# SolarPanel.net
KiCad netlist of a schematic drawn in EAGLE
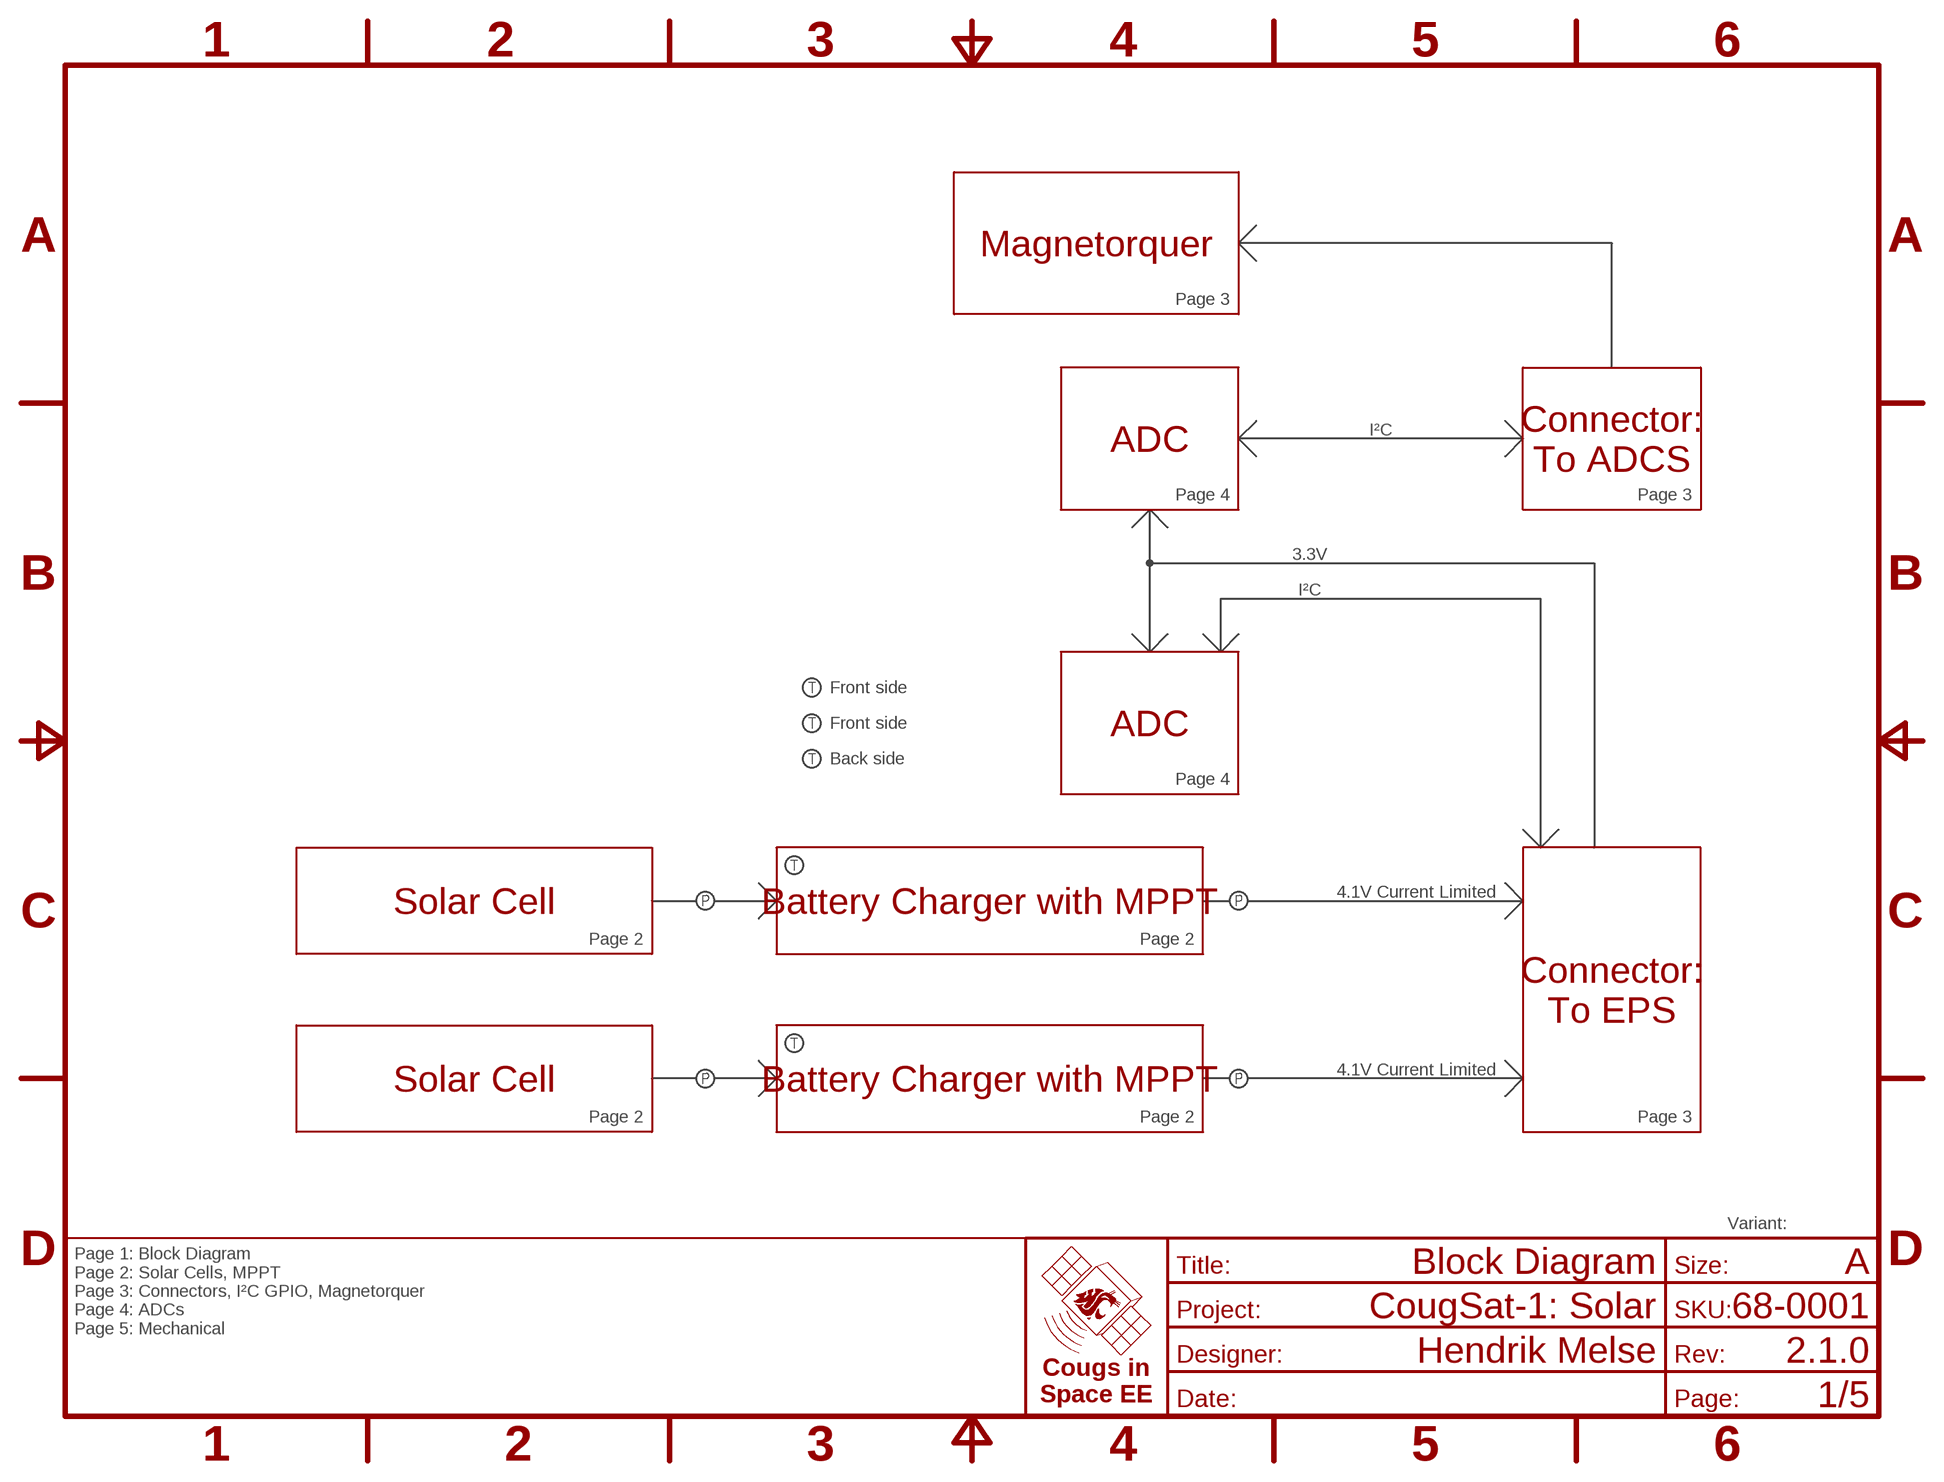
[diagram p0: schematic, sheet 1]
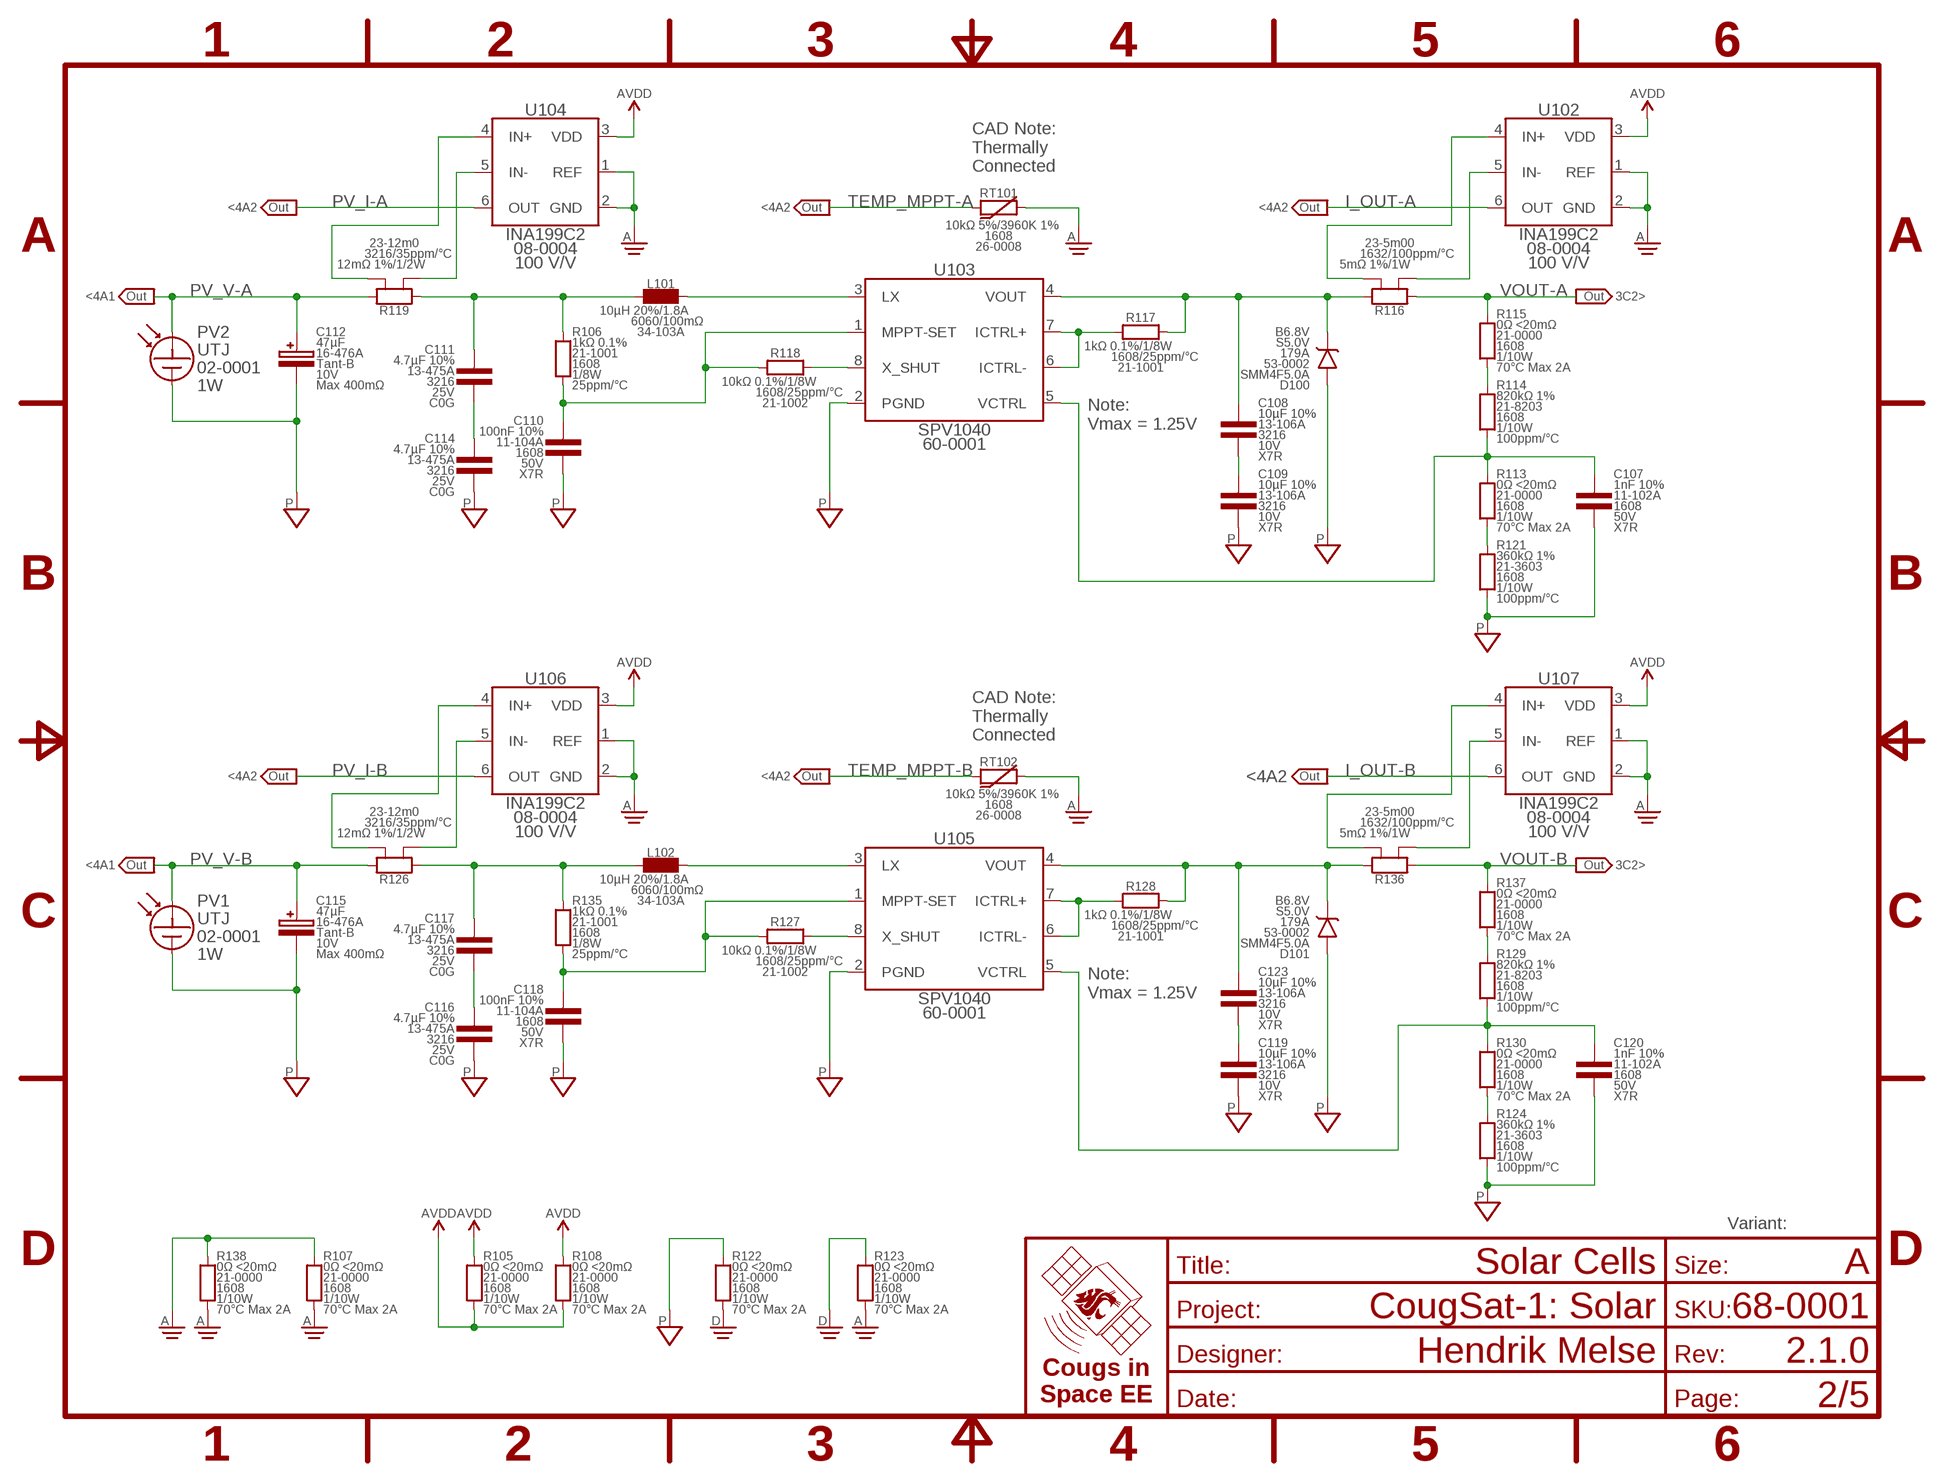
[diagram p1: schematic, sheet 2]
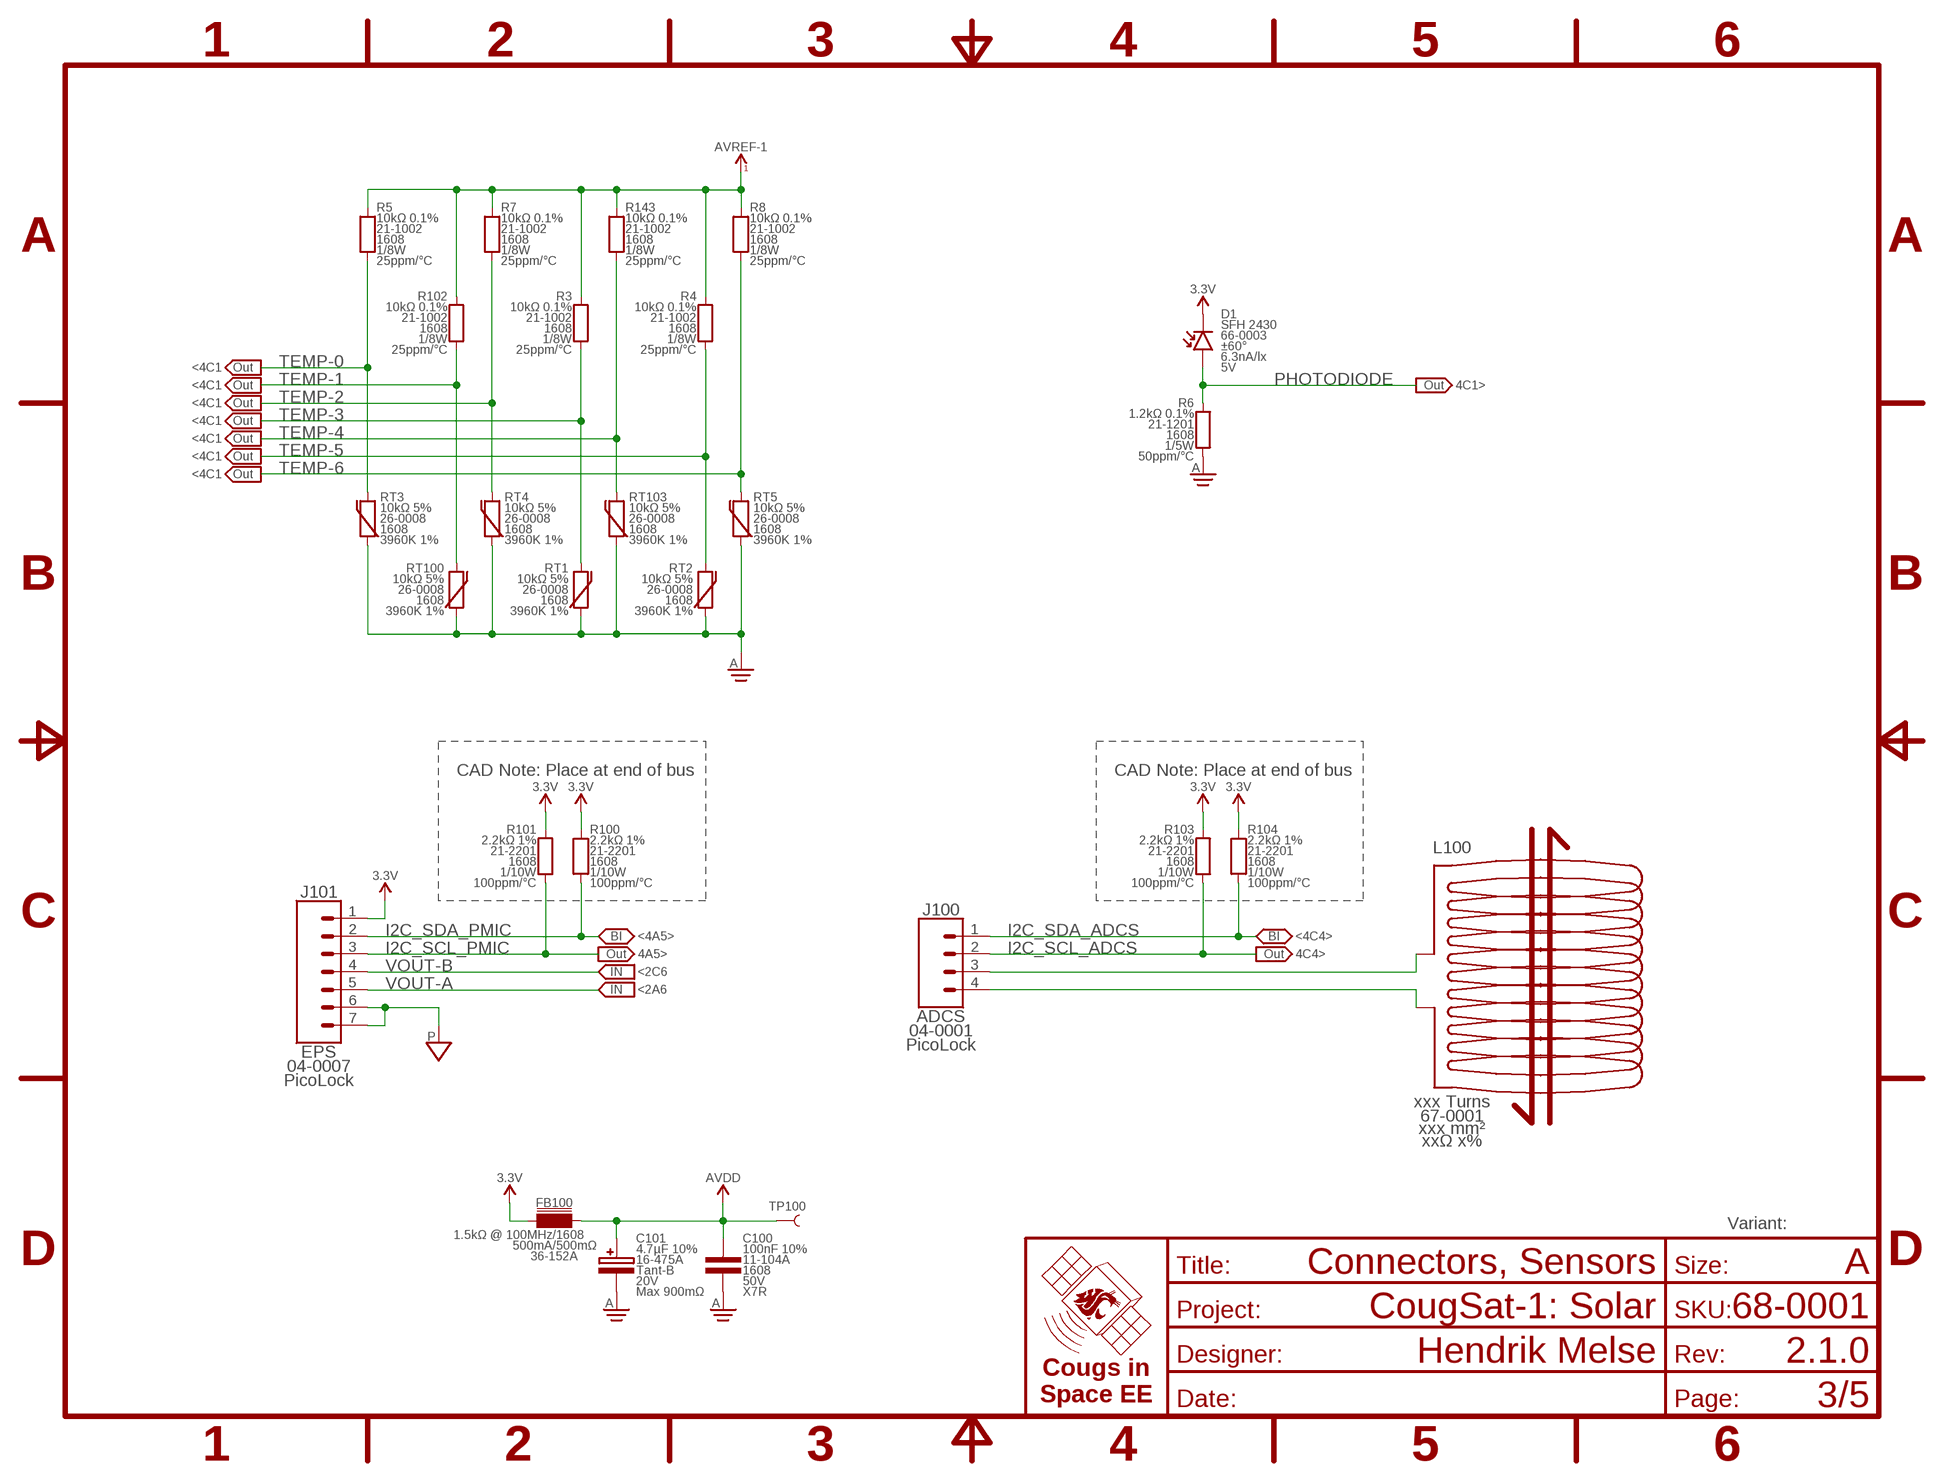
[diagram p2: schematic, sheet 3]
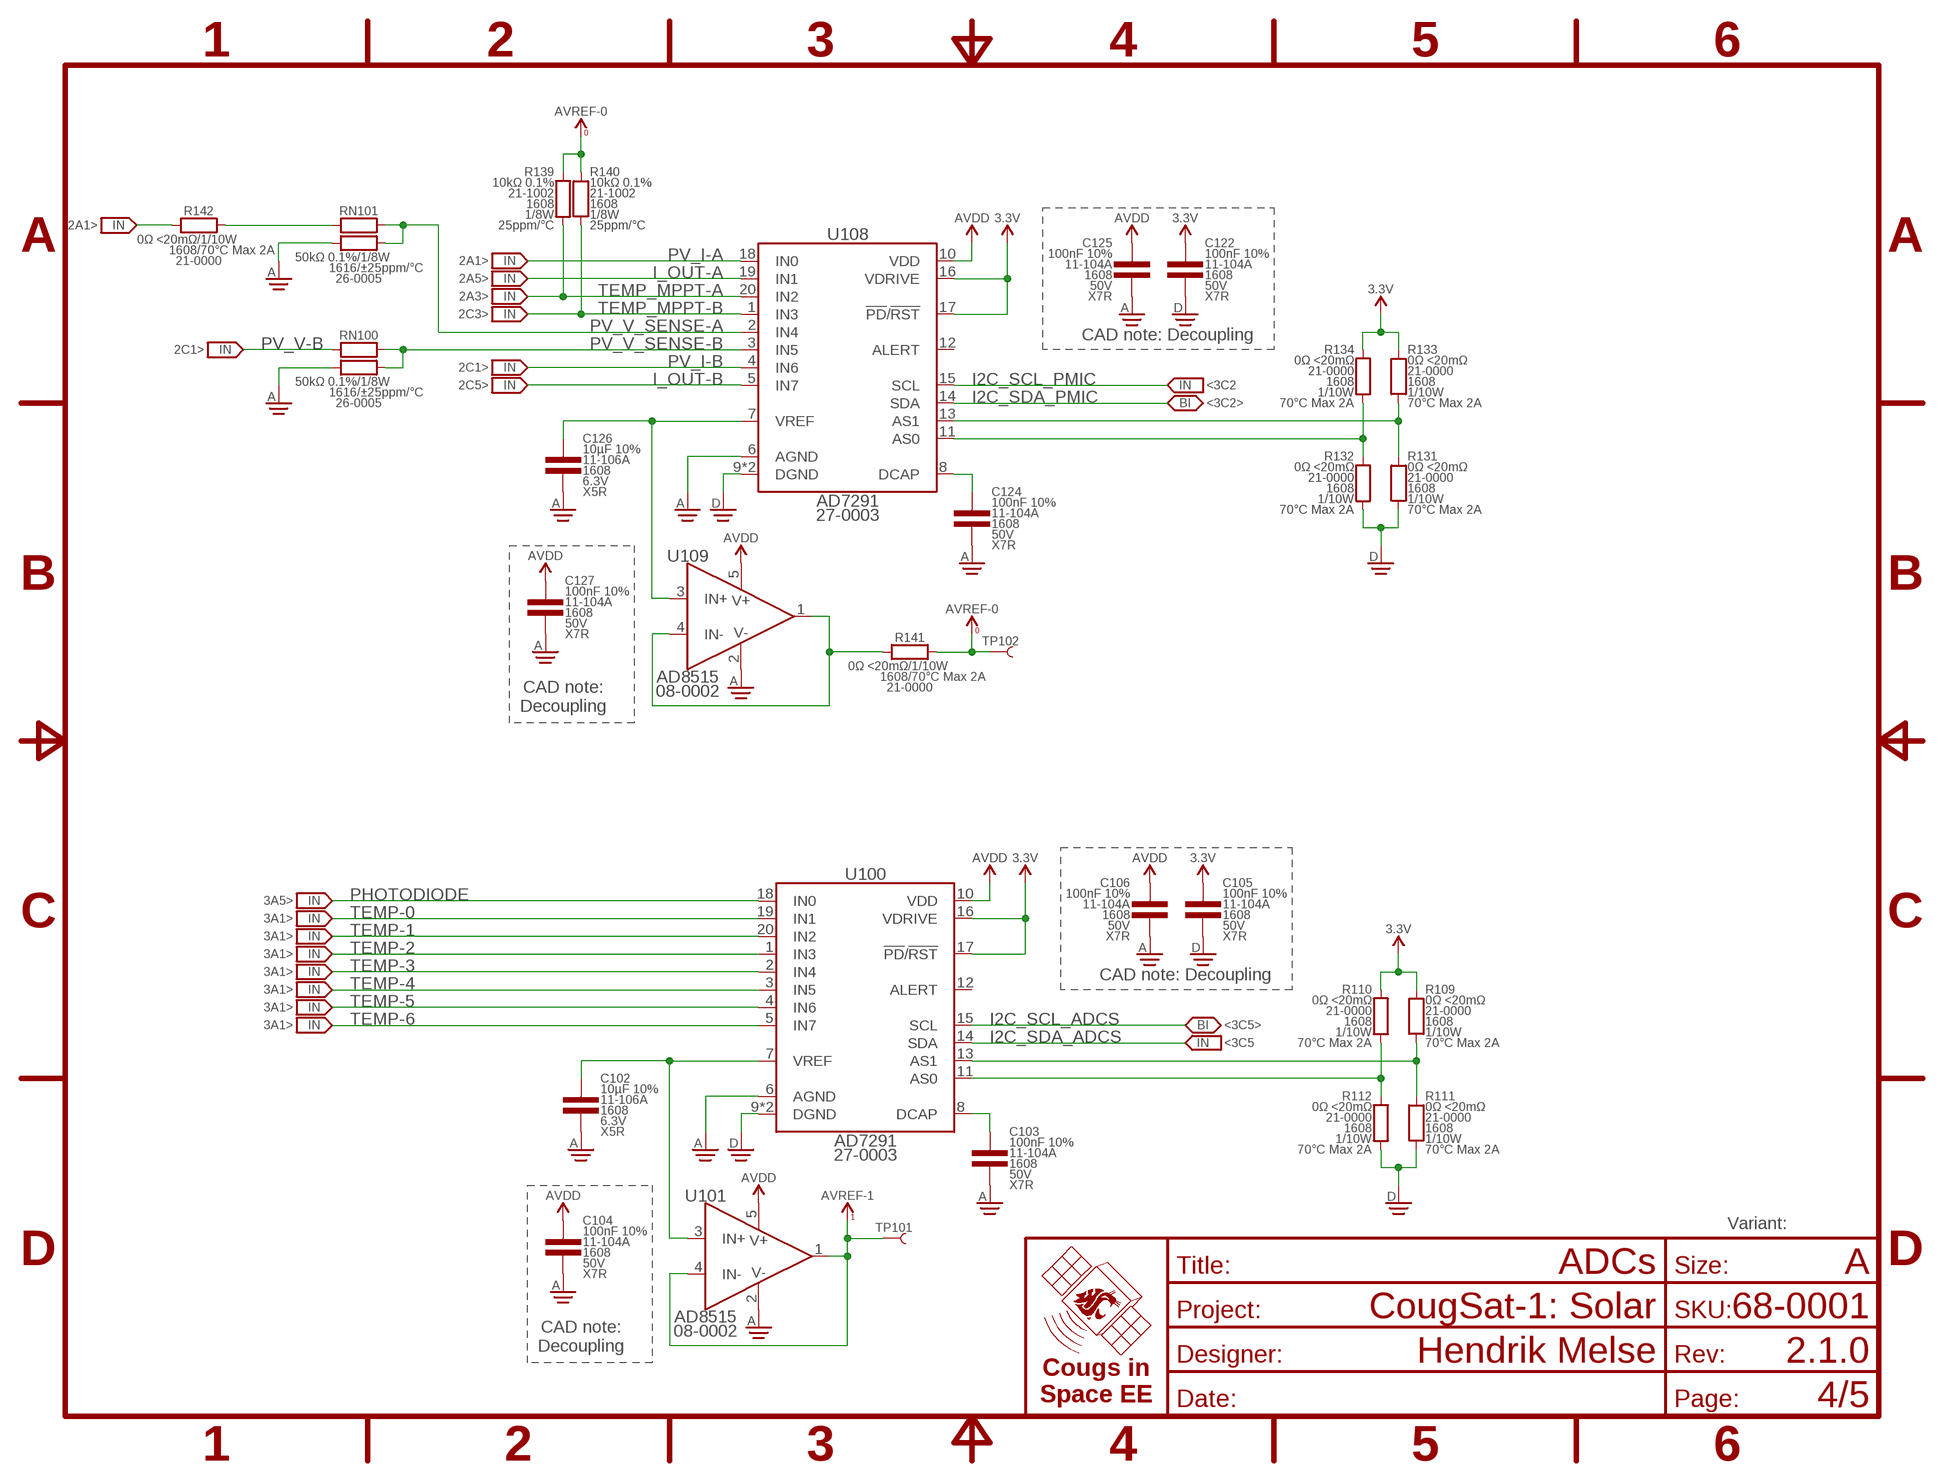
[diagram p3: schematic, sheet 4]
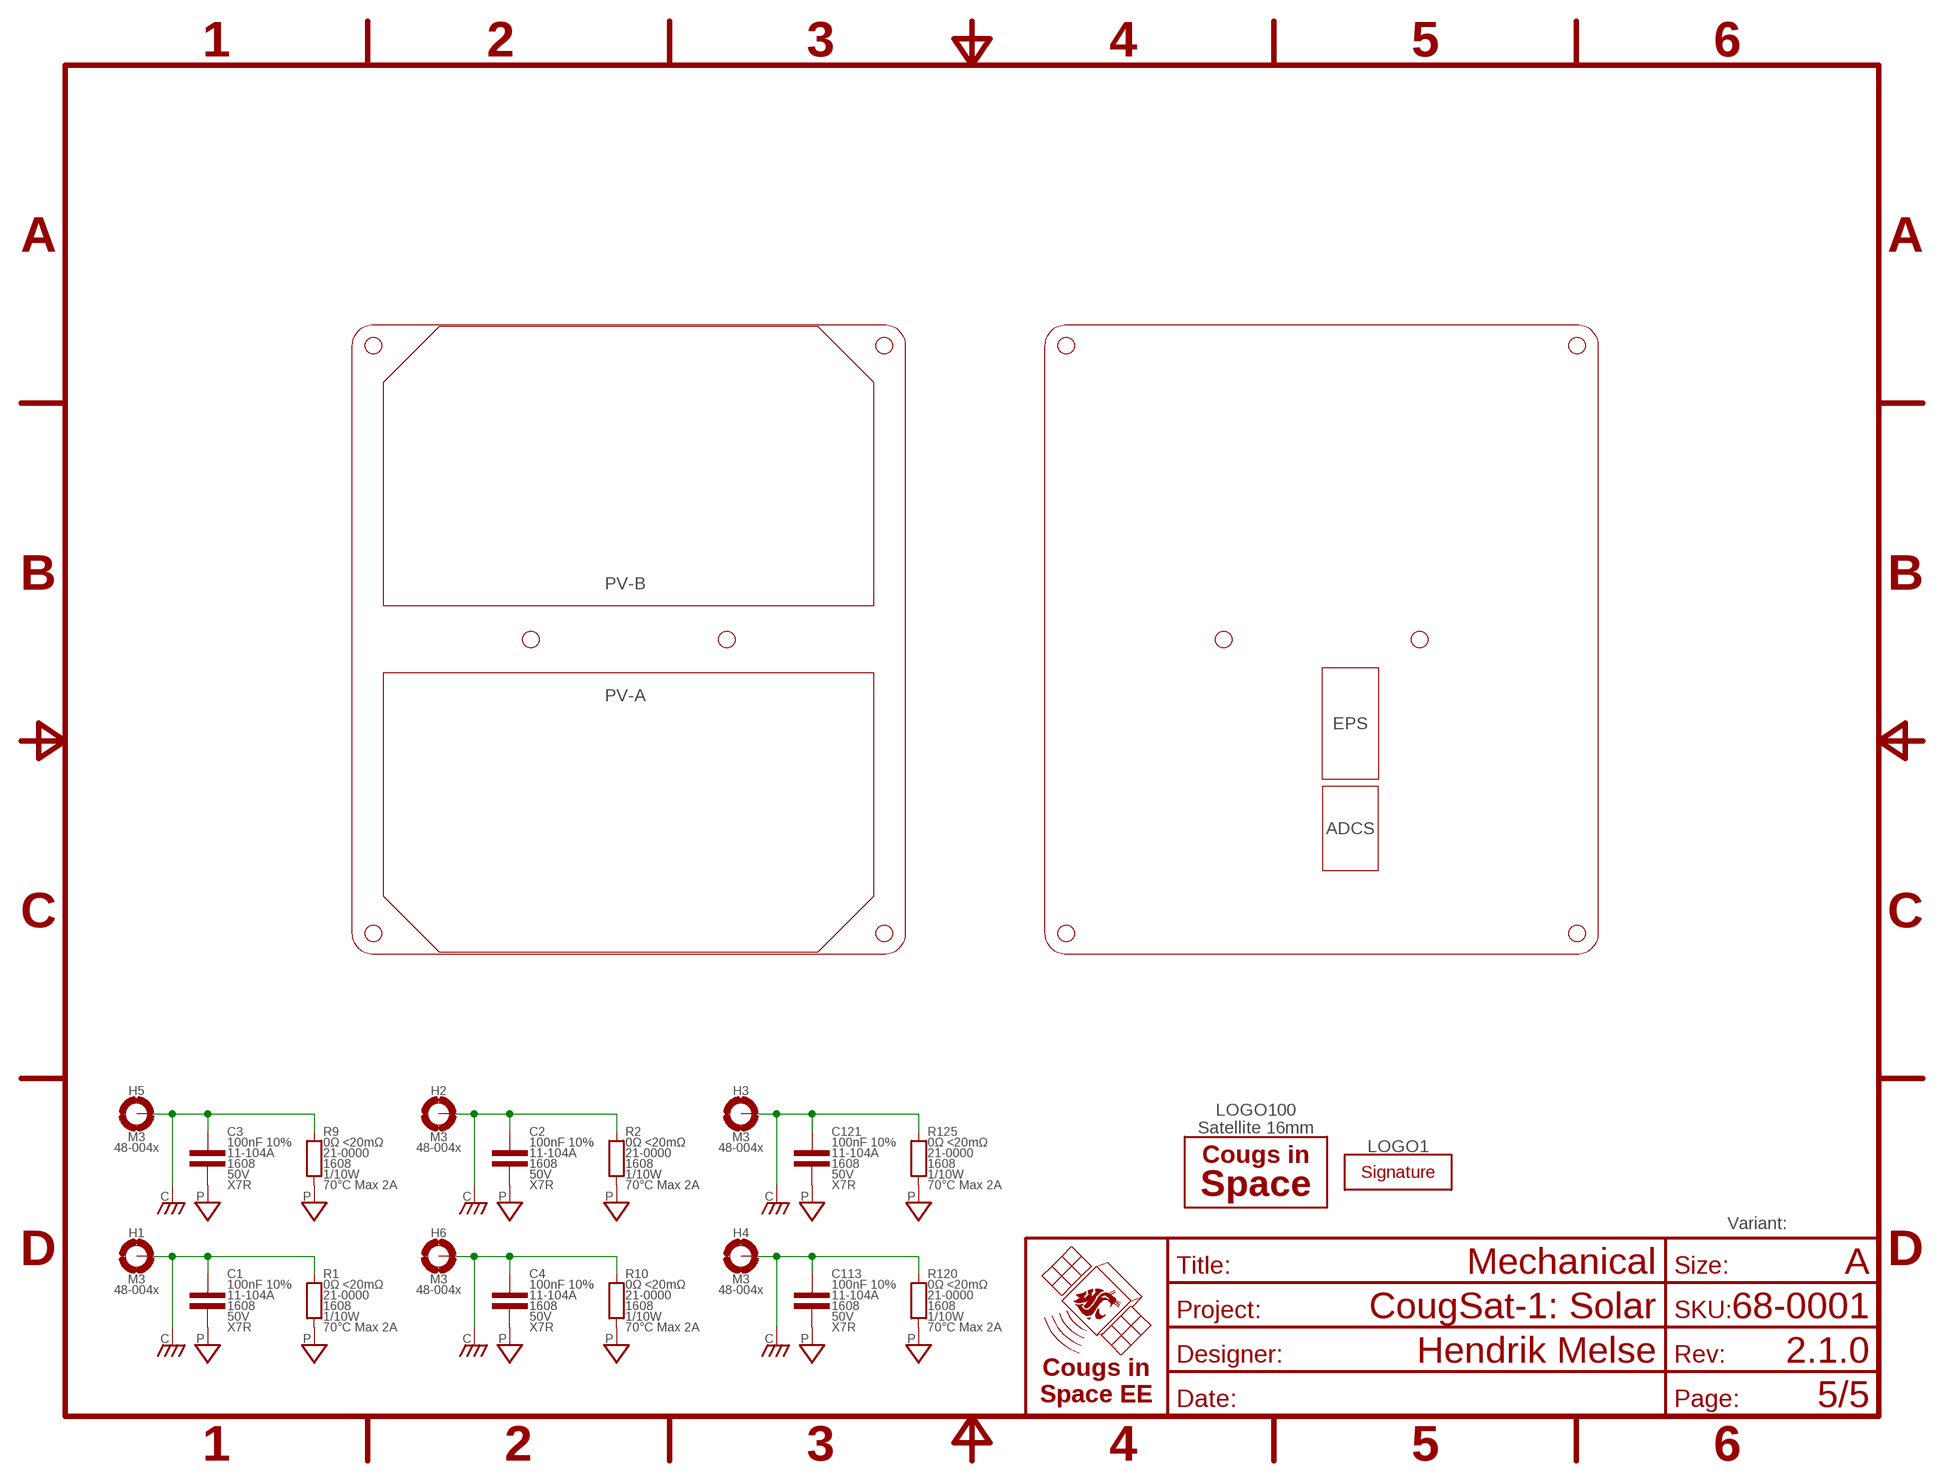
[diagram p4: schematic, sheet 5]

(export (version "E")
  (design (tool "Eeschema 10.0.6"))
  (components
    (comp (ref "C107")
      (value "1nF 10%")
      (footprint "eagle-import:1608")
      (fields
        (field (name "PACKAGE") "1608")
        (field (name "SKU") "11-102A")
        (field (name "TEMP") "X7R")
        (field (name "VOLTAGE") "50V")
      )
      (libsource (lib "eagle-import") (part "CAP-V-1608-1NF"))
    )
    (comp (ref "C108")
      (value "10µF 10%")
      (footprint "eagle-import:3216")
      (fields
        (field (name "PACKAGE") "3216")
        (field (name "SKU") "13-106A")
        (field (name "TEMP") "X7R")
        (field (name "VOLTAGE") "10V")
      )
      (libsource (lib "eagle-import") (part "CAP-V-3216-10UF"))
    )
    (comp (ref "C109")
      (value "10µF 10%")
      (footprint "eagle-import:3216")
      (fields
        (field (name "PACKAGE") "3216")
        (field (name "SKU") "13-106A")
        (field (name "TEMP") "X7R")
        (field (name "VOLTAGE") "10V")
      )
      (libsource (lib "eagle-import") (part "CAP-V-3216-10UF"))
    )
    (comp (ref "C110")
      (value "100nF 10%")
      (footprint "eagle-import:1608")
      (fields
        (field (name "PACKAGE") "1608")
        (field (name "SKU") "11-104A")
        (field (name "TEMP") "X7R")
        (field (name "VOLTAGE") "50V")
      )
      (libsource (lib "eagle-import") (part "CAP-V-1608-100NF"))
    )
    (comp (ref "C111")
      (value "4.7µF 10%")
      (footprint "eagle-import:3216")
      (fields
        (field (name "PACKAGE") "3216")
        (field (name "SKU") "13-475A")
        (field (name "TEMP") "C0G")
        (field (name "VOLTAGE") "25V")
      )
      (libsource (lib "eagle-import") (part "CAP-V-3216-4.7UF"))
    )
    (comp (ref "C112")
      (value "47µF")
      (footprint "eagle-import:4028-POL")
      (fields
        (field (name "ESR") "Max 400mΩ")
        (field (name "PACKAGE") "Tant-B")
        (field (name "SKU") "16-476A")
        (field (name "VOLTAGE") "10V")
      )
      (libsource (lib "eagle-import") (part "CAP-POL-V-4028-47UF"))
    )
    (comp (ref "C114")
      (value "4.7µF 10%")
      (footprint "eagle-import:3216")
      (fields
        (field (name "PACKAGE") "3216")
        (field (name "SKU") "13-475A")
        (field (name "TEMP") "C0G")
        (field (name "VOLTAGE") "25V")
      )
      (libsource (lib "eagle-import") (part "CAP-V-3216-4.7UF"))
    )
    (comp (ref "C115")
      (value "47µF")
      (footprint "eagle-import:4028-POL")
      (fields
        (field (name "ESR") "Max 400mΩ")
        (field (name "PACKAGE") "Tant-B")
        (field (name "SKU") "16-476A")
        (field (name "VOLTAGE") "10V")
      )
      (libsource (lib "eagle-import") (part "CAP-POL-V-4028-47UF"))
    )
    (comp (ref "C116")
      (value "4.7µF 10%")
      (footprint "eagle-import:3216")
      (fields
        (field (name "PACKAGE") "3216")
        (field (name "SKU") "13-475A")
        (field (name "TEMP") "C0G")
        (field (name "VOLTAGE") "25V")
      )
      (libsource (lib "eagle-import") (part "CAP-V-3216-4.7UF"))
    )
    (comp (ref "C117")
      (value "4.7µF 10%")
      (footprint "eagle-import:3216")
      (fields
        (field (name "PACKAGE") "3216")
        (field (name "SKU") "13-475A")
        (field (name "TEMP") "C0G")
        (field (name "VOLTAGE") "25V")
      )
      (libsource (lib "eagle-import") (part "CAP-V-3216-4.7UF"))
    )
    (comp (ref "C118")
      (value "100nF 10%")
      (footprint "eagle-import:1608")
      (fields
        (field (name "PACKAGE") "1608")
        (field (name "SKU") "11-104A")
        (field (name "TEMP") "X7R")
        (field (name "VOLTAGE") "50V")
      )
      (libsource (lib "eagle-import") (part "CAP-V-1608-100NF"))
    )
    (comp (ref "C119")
      (value "10µF 10%")
      (footprint "eagle-import:3216")
      (fields
        (field (name "PACKAGE") "3216")
        (field (name "SKU") "13-106A")
        (field (name "TEMP") "X7R")
        (field (name "VOLTAGE") "10V")
      )
      (libsource (lib "eagle-import") (part "CAP-V-3216-10UF"))
    )
    (comp (ref "C120")
      (value "1nF 10%")
      (footprint "eagle-import:1608")
      (fields
        (field (name "PACKAGE") "1608")
        (field (name "SKU") "11-102A")
        (field (name "TEMP") "X7R")
        (field (name "VOLTAGE") "50V")
      )
      (libsource (lib "eagle-import") (part "CAP-V-1608-1NF"))
    )
    (comp (ref "C123")
      (value "10µF 10%")
      (footprint "eagle-import:3216")
      (fields
        (field (name "PACKAGE") "3216")
        (field (name "SKU") "13-106A")
        (field (name "TEMP") "X7R")
        (field (name "VOLTAGE") "10V")
      )
      (libsource (lib "eagle-import") (part "CAP-V-3216-10UF"))
    )
    (comp (ref "D100")
      (value "SMM4F5.0A")
      (footprint "eagle-import:STMITE")
      (fields
        (field (name "CURRENT") "179A")
        (field (name "SKU") "53-0002")
        (field (name "VB") "B6.8V")
        (field (name "VS") "S5.0V")
      )
      (libsource (lib "eagle-import") (part "DIODE-TVS-V-STMITE-5.0"))
    )
    (comp (ref "D101")
      (value "SMM4F5.0A")
      (footprint "eagle-import:STMITE")
      (fields
        (field (name "CURRENT") "179A")
        (field (name "SKU") "53-0002")
        (field (name "VB") "B6.8V")
        (field (name "VS") "S5.0V")
      )
      (libsource (lib "eagle-import") (part "DIODE-TVS-V-STMITE-5.0"))
    )
    (comp (ref "L101")
      (value "10µH 20%")
      (footprint "eagle-import:6060")
      (fields
        (field (name "CURRENT") "1.8A")
        (field (name "DCR") "100mΩ")
        (field (name "PACKAGE") "6060")
        (field (name "SKU") "34-103A")
      )
      (libsource (lib "eagle-import") (part "INDUCTOR-H-6060-10UH"))
    )
    (comp (ref "L102")
      (value "10µH 20%")
      (footprint "eagle-import:6060")
      (fields
        (field (name "CURRENT") "1.8A")
        (field (name "DCR") "100mΩ")
        (field (name "PACKAGE") "6060")
        (field (name "SKU") "34-103A")
      )
      (libsource (lib "eagle-import") (part "INDUCTOR-H-6060-10UH"))
    )
    (comp (ref "PV1")
      (value "UTJ")
      (footprint "eagle-import:SPECTROLABS-UTJ")
      (fields (field (name "SKU") "02-0001") (field (name "POWER") "1W"))
      (libsource (lib "eagle-import") (part "SOLAR_CELL-UTJ"))
    )
    (comp (ref "PV2")
      (value "UTJ")
      (footprint "eagle-import:SPECTROLABS-UTJ")
      (fields (field (name "SKU") "02-0001") (field (name "POWER") "1W"))
      (libsource (lib "eagle-import") (part "SOLAR_CELL-UTJ"))
    )
    (comp (ref "R105")
      (value "0Ω <20mΩ")
      (footprint "eagle-import:1608")
      (fields
        (field (name "PACKAGE") "1608")
        (field (name "POWER") "1/10W")
        (field (name "SKU") "21-0000")
        (field (name "TEMP") "70°C Max 2A")
      )
      (libsource (lib "eagle-import") (part "RES-V-1608-0"))
    )
    (comp (ref "R106")
      (value "1kΩ 0.1%")
      (footprint "eagle-import:1608")
      (fields
        (field (name "PACKAGE") "1608")
        (field (name "POWER") "1/8W")
        (field (name "SKU") "21-1001")
        (field (name "TEMP") "25ppm/°C")
      )
      (libsource (lib "eagle-import") (part "RES-V-1608-1K"))
    )
    (comp (ref "R107")
      (value "0Ω <20mΩ")
      (footprint "eagle-import:1608")
      (fields
        (field (name "PACKAGE") "1608")
        (field (name "POWER") "1/10W")
        (field (name "SKU") "21-0000")
        (field (name "TEMP") "70°C Max 2A")
      )
      (libsource (lib "eagle-import") (part "RES-V-1608-0"))
    )
    (comp (ref "R108")
      (value "0Ω <20mΩ")
      (footprint "eagle-import:1608")
      (fields
        (field (name "PACKAGE") "1608")
        (field (name "POWER") "1/10W")
        (field (name "SKU") "21-0000")
        (field (name "TEMP") "70°C Max 2A")
      )
      (libsource (lib "eagle-import") (part "RES-V-1608-0"))
    )
    (comp (ref "R113")
      (value "0Ω <20mΩ")
      (footprint "eagle-import:1608")
      (fields
        (field (name "PACKAGE") "1608")
        (field (name "POWER") "1/10W")
        (field (name "SKU") "21-0000")
        (field (name "TEMP") "70°C Max 2A")
      )
      (libsource (lib "eagle-import") (part "RES-V-1608-0"))
    )
    (comp (ref "R114")
      (value "820kΩ 1%")
      (footprint "eagle-import:1608")
      (fields
        (field (name "PACKAGE") "1608")
        (field (name "POWER") "1/10W")
        (field (name "SKU") "21-8203")
        (field (name "TEMP") "100ppm/°C")
      )
      (libsource (lib "eagle-import") (part "RES-V-1608-820K"))
    )
    (comp (ref "R115")
      (value "0Ω <20mΩ")
      (footprint "eagle-import:1608")
      (fields
        (field (name "PACKAGE") "1608")
        (field (name "POWER") "1/10W")
        (field (name "SKU") "21-0000")
        (field (name "TEMP") "70°C Max 2A")
      )
      (libsource (lib "eagle-import") (part "RES-V-1608-0"))
    )
    (comp (ref "R116")
      (value "5mΩ 1%")
      (footprint "eagle-import:1632-KELVIN")
      (fields
        (field (name "PACKAGE") "1632")
        (field (name "POWER") "1W")
        (field (name "SKU") "23-5m00")
        (field (name "TEMP") "100ppm/°C")
      )
      (libsource (lib "eagle-import") (part "RES-H-KELVIN-1632-0.005R"))
    )
    (comp (ref "R117")
      (value "1kΩ 0.1%")
      (footprint "eagle-import:1608")
      (fields
        (field (name "PACKAGE") "1608")
        (field (name "POWER") "1/8W")
        (field (name "SKU") "21-1001")
        (field (name "TEMP") "25ppm/°C")
      )
      (libsource (lib "eagle-import") (part "RES-H-1608-1K"))
    )
    (comp (ref "R118")
      (value "10kΩ 0.1%")
      (footprint "eagle-import:1608")
      (fields
        (field (name "PACKAGE") "1608")
        (field (name "POWER") "1/8W")
        (field (name "SKU") "21-1002")
        (field (name "TEMP") "25ppm/°C")
      )
      (libsource (lib "eagle-import") (part "RES-H-1608-10K"))
    )
    (comp (ref "R119")
      (value "12mΩ 1%")
      (footprint "eagle-import:3216-KELVIN")
      (fields
        (field (name "PACKAGE") "3216")
        (field (name "POWER") "1/2W")
        (field (name "SKU") "23-12m0")
        (field (name "TEMP") "35ppm/°C")
      )
      (libsource (lib "eagle-import") (part "RES-H-KELVIN-3216-0.012R"))
    )
    (comp (ref "R121")
      (value "360kΩ 1%")
      (footprint "eagle-import:1608")
      (fields
        (field (name "PACKAGE") "1608")
        (field (name "POWER") "1/10W")
        (field (name "SKU") "21-3603")
        (field (name "TEMP") "100ppm/°C")
      )
      (libsource (lib "eagle-import") (part "RES-V-1608-360K"))
    )
    (comp (ref "R122")
      (value "0Ω <20mΩ")
      (footprint "eagle-import:1608")
      (fields
        (field (name "PACKAGE") "1608")
        (field (name "POWER") "1/10W")
        (field (name "SKU") "21-0000")
        (field (name "TEMP") "70°C Max 2A")
      )
      (libsource (lib "eagle-import") (part "RES-V-1608-0"))
    )
    (comp (ref "R123")
      (value "0Ω <20mΩ")
      (footprint "eagle-import:1608")
      (fields
        (field (name "PACKAGE") "1608")
        (field (name "POWER") "1/10W")
        (field (name "SKU") "21-0000")
        (field (name "TEMP") "70°C Max 2A")
      )
      (libsource (lib "eagle-import") (part "RES-V-1608-0"))
    )
    (comp (ref "R124")
      (value "360kΩ 1%")
      (footprint "eagle-import:1608")
      (fields
        (field (name "PACKAGE") "1608")
        (field (name "POWER") "1/10W")
        (field (name "SKU") "21-3603")
        (field (name "TEMP") "100ppm/°C")
      )
      (libsource (lib "eagle-import") (part "RES-V-1608-360K"))
    )
    (comp (ref "R126")
      (value "12mΩ 1%")
      (footprint "eagle-import:3216-KELVIN")
      (fields
        (field (name "PACKAGE") "3216")
        (field (name "POWER") "1/2W")
        (field (name "SKU") "23-12m0")
        (field (name "TEMP") "35ppm/°C")
      )
      (libsource (lib "eagle-import") (part "RES-H-KELVIN-3216-0.012R"))
    )
    (comp (ref "R127")
      (value "10kΩ 0.1%")
      (footprint "eagle-import:1608")
      (fields
        (field (name "PACKAGE") "1608")
        (field (name "POWER") "1/8W")
        (field (name "SKU") "21-1002")
        (field (name "TEMP") "25ppm/°C")
      )
      (libsource (lib "eagle-import") (part "RES-H-1608-10K"))
    )
    (comp (ref "R128")
      (value "1kΩ 0.1%")
      (footprint "eagle-import:1608")
      (fields
        (field (name "PACKAGE") "1608")
        (field (name "POWER") "1/8W")
        (field (name "SKU") "21-1001")
        (field (name "TEMP") "25ppm/°C")
      )
      (libsource (lib "eagle-import") (part "RES-H-1608-1K"))
    )
    (comp (ref "R129")
      (value "820kΩ 1%")
      (footprint "eagle-import:1608")
      (fields
        (field (name "PACKAGE") "1608")
        (field (name "POWER") "1/10W")
        (field (name "SKU") "21-8203")
        (field (name "TEMP") "100ppm/°C")
      )
      (libsource (lib "eagle-import") (part "RES-V-1608-820K"))
    )
    (comp (ref "R130")
      (value "0Ω <20mΩ")
      (footprint "eagle-import:1608")
      (fields
        (field (name "PACKAGE") "1608")
        (field (name "POWER") "1/10W")
        (field (name "SKU") "21-0000")
        (field (name "TEMP") "70°C Max 2A")
      )
      (libsource (lib "eagle-import") (part "RES-V-1608-0"))
    )
    (comp (ref "R135")
      (value "1kΩ 0.1%")
      (footprint "eagle-import:1608")
      (fields
        (field (name "PACKAGE") "1608")
        (field (name "POWER") "1/8W")
        (field (name "SKU") "21-1001")
        (field (name "TEMP") "25ppm/°C")
      )
      (libsource (lib "eagle-import") (part "RES-V-1608-1K"))
    )
    (comp (ref "R136")
      (value "5mΩ 1%")
      (footprint "eagle-import:1632-KELVIN")
      (fields
        (field (name "PACKAGE") "1632")
        (field (name "POWER") "1W")
        (field (name "SKU") "23-5m00")
        (field (name "TEMP") "100ppm/°C")
      )
      (libsource (lib "eagle-import") (part "RES-H-KELVIN-1632-0.005R"))
    )
    (comp (ref "R137")
      (value "0Ω <20mΩ")
      (footprint "eagle-import:1608")
      (fields
        (field (name "PACKAGE") "1608")
        (field (name "POWER") "1/10W")
        (field (name "SKU") "21-0000")
        (field (name "TEMP") "70°C Max 2A")
      )
      (libsource (lib "eagle-import") (part "RES-V-1608-0"))
    )
    (comp (ref "R138")
      (value "0Ω <20mΩ")
      (footprint "eagle-import:1608")
      (fields
        (field (name "PACKAGE") "1608")
        (field (name "POWER") "1/10W")
        (field (name "SKU") "21-0000")
        (field (name "TEMP") "70°C Max 2A")
      )
      (libsource (lib "eagle-import") (part "RES-V-1608-0"))
    )
    (comp (ref "RT101")
      (value "10kΩ 5%")
      (footprint "eagle-import:1608")
      (fields
        (field (name "B2585") "3960K 1%")
        (field (name "PACKAGE") "1608")
        (field (name "SKU") "26-0008")
      )
      (libsource (lib "eagle-import") (part "THERMISTOR-H-1608-10K"))
    )
    (comp (ref "RT102")
      (value "10kΩ 5%")
      (footprint "eagle-import:1608")
      (fields
        (field (name "B2585") "3960K 1%")
        (field (name "PACKAGE") "1608")
        (field (name "SKU") "26-0008")
      )
      (libsource (lib "eagle-import") (part "THERMISTOR-H-1608-10K"))
    )
    (comp (ref "U102")
      (value "INA199C2")
      (footprint "eagle-import:SOT363")
      (fields (field (name "GAIN") "100 V/V") (field (name "SKU") "08-0004"))
      (libsource (lib "eagle-import") (part "INA199C2"))
    )
    (comp (ref "U103")
      (value "SPV1040")
      (footprint "eagle-import:TSSOP8")
      (fields (field (name "SKU") "60-0001"))
      (libsource (lib "eagle-import") (part "SPV1040"))
    )
    (comp (ref "U104")
      (value "INA199C2")
      (footprint "eagle-import:SOT363")
      (fields (field (name "GAIN") "100 V/V") (field (name "SKU") "08-0004"))
      (libsource (lib "eagle-import") (part "INA199C2"))
    )
    (comp (ref "U105")
      (value "SPV1040")
      (footprint "eagle-import:TSSOP8")
      (fields (field (name "SKU") "60-0001"))
      (libsource (lib "eagle-import") (part "SPV1040"))
    )
    (comp (ref "U106")
      (value "INA199C2")
      (footprint "eagle-import:SOT363")
      (fields (field (name "GAIN") "100 V/V") (field (name "SKU") "08-0004"))
      (libsource (lib "eagle-import") (part "INA199C2"))
    )
    (comp (ref "U107")
      (value "INA199C2")
      (footprint "eagle-import:SOT363")
      (fields (field (name "GAIN") "100 V/V") (field (name "SKU") "08-0004"))
      (libsource (lib "eagle-import") (part "INA199C2"))
    )
    (comp (ref "C102")
      (value "10µF 10%")
      (footprint "eagle-import:1608")
      (fields
        (field (name "PACKAGE") "1608")
        (field (name "SKU") "11-106A")
        (field (name "TEMP") "X5R")
        (field (name "VOLTAGE") "6.3V")
      )
      (libsource (lib "eagle-import") (part "CAP-V-1608-10UF"))
    )
    (comp (ref "C103")
      (value "100nF 10%")
      (footprint "eagle-import:1608")
      (fields
        (field (name "PACKAGE") "1608")
        (field (name "SKU") "11-104A")
        (field (name "TEMP") "X7R")
        (field (name "VOLTAGE") "50V")
      )
      (libsource (lib "eagle-import") (part "CAP-V-1608-100NF"))
    )
    (comp (ref "C104")
      (value "100nF 10%")
      (footprint "eagle-import:1608")
      (fields
        (field (name "PACKAGE") "1608")
        (field (name "SKU") "11-104A")
        (field (name "TEMP") "X7R")
        (field (name "VOLTAGE") "50V")
      )
      (libsource (lib "eagle-import") (part "CAP-V-1608-100NF"))
    )
    (comp (ref "C105")
      (value "100nF 10%")
      (footprint "eagle-import:1608")
      (fields
        (field (name "PACKAGE") "1608")
        (field (name "SKU") "11-104A")
        (field (name "TEMP") "X7R")
        (field (name "VOLTAGE") "50V")
      )
      (libsource (lib "eagle-import") (part "CAP-V-1608-100NF"))
    )
    (comp (ref "C106")
      (value "100nF 10%")
      (footprint "eagle-import:1608")
      (fields
        (field (name "PACKAGE") "1608")
        (field (name "SKU") "11-104A")
        (field (name "TEMP") "X7R")
        (field (name "VOLTAGE") "50V")
      )
      (libsource (lib "eagle-import") (part "CAP-V-1608-100NF"))
    )
    (comp (ref "C122")
      (value "100nF 10%")
      (footprint "eagle-import:1608")
      (fields
        (field (name "PACKAGE") "1608")
        (field (name "SKU") "11-104A")
        (field (name "TEMP") "X7R")
        (field (name "VOLTAGE") "50V")
      )
      (libsource (lib "eagle-import") (part "CAP-V-1608-100NF"))
    )
    (comp (ref "C124")
      (value "100nF 10%")
      (footprint "eagle-import:1608")
      (fields
        (field (name "PACKAGE") "1608")
        (field (name "SKU") "11-104A")
        (field (name "TEMP") "X7R")
        (field (name "VOLTAGE") "50V")
      )
      (libsource (lib "eagle-import") (part "CAP-V-1608-100NF"))
    )
    (comp (ref "C125")
      (value "100nF 10%")
      (footprint "eagle-import:1608")
      (fields
        (field (name "PACKAGE") "1608")
        (field (name "SKU") "11-104A")
        (field (name "TEMP") "X7R")
        (field (name "VOLTAGE") "50V")
      )
      (libsource (lib "eagle-import") (part "CAP-V-1608-100NF"))
    )
    (comp (ref "C126")
      (value "10µF 10%")
      (footprint "eagle-import:1608")
      (fields
        (field (name "PACKAGE") "1608")
        (field (name "SKU") "11-106A")
        (field (name "TEMP") "X5R")
        (field (name "VOLTAGE") "6.3V")
      )
      (libsource (lib "eagle-import") (part "CAP-V-1608-10UF"))
    )
    (comp (ref "C127")
      (value "100nF 10%")
      (footprint "eagle-import:1608")
      (fields
        (field (name "PACKAGE") "1608")
        (field (name "SKU") "11-104A")
        (field (name "TEMP") "X7R")
        (field (name "VOLTAGE") "50V")
      )
      (libsource (lib "eagle-import") (part "CAP-V-1608-100NF"))
    )
    (comp (ref "R109")
      (value "0Ω <20mΩ")
      (footprint "eagle-import:1608")
      (fields
        (field (name "PACKAGE") "1608")
        (field (name "POWER") "1/10W")
        (field (name "SKU") "21-0000")
        (field (name "TEMP") "70°C Max 2A")
      )
      (libsource (lib "eagle-import") (part "RES-V-1608-0"))
    )
    (comp (ref "R110")
      (value "0Ω <20mΩ")
      (footprint "eagle-import:1608")
      (fields
        (field (name "PACKAGE") "1608")
        (field (name "POWER") "1/10W")
        (field (name "SKU") "21-0000")
        (field (name "TEMP") "70°C Max 2A")
      )
      (libsource (lib "eagle-import") (part "RES-V-1608-0"))
    )
    (comp (ref "R111")
      (value "0Ω <20mΩ")
      (footprint "eagle-import:1608")
      (fields
        (field (name "PACKAGE") "1608")
        (field (name "POWER") "1/10W")
        (field (name "SKU") "21-0000")
        (field (name "TEMP") "70°C Max 2A")
      )
      (libsource (lib "eagle-import") (part "RES-V-1608-0"))
    )
    (comp (ref "R112")
      (value "0Ω <20mΩ")
      (footprint "eagle-import:1608")
      (fields
        (field (name "PACKAGE") "1608")
        (field (name "POWER") "1/10W")
        (field (name "SKU") "21-0000")
        (field (name "TEMP") "70°C Max 2A")
      )
      (libsource (lib "eagle-import") (part "RES-V-1608-0"))
    )
    (comp (ref "R131")
      (value "0Ω <20mΩ")
      (footprint "eagle-import:1608")
      (fields
        (field (name "PACKAGE") "1608")
        (field (name "POWER") "1/10W")
        (field (name "SKU") "21-0000")
        (field (name "TEMP") "70°C Max 2A")
      )
      (libsource (lib "eagle-import") (part "RES-V-1608-0"))
    )
    (comp (ref "R132")
      (value "0Ω <20mΩ")
      (footprint "eagle-import:1608")
      (fields
        (field (name "PACKAGE") "1608")
        (field (name "POWER") "1/10W")
        (field (name "SKU") "21-0000")
        (field (name "TEMP") "70°C Max 2A")
      )
      (libsource (lib "eagle-import") (part "RES-V-1608-0"))
    )
    (comp (ref "R133")
      (value "0Ω <20mΩ")
      (footprint "eagle-import:1608")
      (fields
        (field (name "PACKAGE") "1608")
        (field (name "POWER") "1/10W")
        (field (name "SKU") "21-0000")
        (field (name "TEMP") "70°C Max 2A")
      )
      (libsource (lib "eagle-import") (part "RES-V-1608-0"))
    )
    (comp (ref "R134")
      (value "0Ω <20mΩ")
      (footprint "eagle-import:1608")
      (fields
        (field (name "PACKAGE") "1608")
        (field (name "POWER") "1/10W")
        (field (name "SKU") "21-0000")
        (field (name "TEMP") "70°C Max 2A")
      )
      (libsource (lib "eagle-import") (part "RES-V-1608-0"))
    )
    (comp (ref "R139")
      (value "10kΩ 0.1%")
      (footprint "eagle-import:1608")
      (fields
        (field (name "PACKAGE") "1608")
        (field (name "POWER") "1/8W")
        (field (name "SKU") "21-1002")
        (field (name "TEMP") "25ppm/°C")
      )
      (libsource (lib "eagle-import") (part "RES-V-1608-10K"))
    )
    (comp (ref "R140")
      (value "10kΩ 0.1%")
      (footprint "eagle-import:1608")
      (fields
        (field (name "PACKAGE") "1608")
        (field (name "POWER") "1/8W")
        (field (name "SKU") "21-1002")
        (field (name "TEMP") "25ppm/°C")
      )
      (libsource (lib "eagle-import") (part "RES-V-1608-10K"))
    )
    (comp (ref "R141")
      (value "0Ω <20mΩ")
      (footprint "eagle-import:1608")
      (fields
        (field (name "PACKAGE") "1608")
        (field (name "POWER") "1/10W")
        (field (name "SKU") "21-0000")
        (field (name "TEMP") "70°C Max 2A")
      )
      (libsource (lib "eagle-import") (part "RES-H-1608-0"))
    )
    (comp (ref "R142")
      (value "0Ω <20mΩ")
      (footprint "eagle-import:1608")
      (fields
        (field (name "PACKAGE") "1608")
        (field (name "POWER") "1/10W")
        (field (name "SKU") "21-0000")
        (field (name "TEMP") "70°C Max 2A")
      )
      (libsource (lib "eagle-import") (part "RES-H-1608-0"))
    )
    (comp (ref "RN100")
      (value "50kΩ 0.1%")
      (footprint "eagle-import:1616")
      (fields
        (field (name "PACKAGE") "1616")
        (field (name "POWER") "1/8W")
        (field (name "SKU") "26-0005")
        (field (name "TEMP") "±25ppm/°C")
      )
      (libsource (lib "eagle-import") (part "RES-H-PAIRED-1616-50K"))
    )
    (comp (ref "RN101")
      (value "50kΩ 0.1%")
      (footprint "eagle-import:1616")
      (fields
        (field (name "PACKAGE") "1616")
        (field (name "POWER") "1/8W")
        (field (name "SKU") "26-0005")
        (field (name "TEMP") "±25ppm/°C")
      )
      (libsource (lib "eagle-import") (part "RES-H-PAIRED-1616-50K"))
    )
    (comp (ref "TP101")
      (value "TEST_POINT-SMD-C-1.25")
      (footprint "eagle-import:SMD-C-1.25")
      (libsource (lib "eagle-import") (part "TEST_POINT-SMD-C-1.25"))
    )
    (comp (ref "TP102")
      (value "TEST_POINT-SMD-C-1.25")
      (footprint "eagle-import:SMD-C-1.25")
      (libsource (lib "eagle-import") (part "TEST_POINT-SMD-C-1.25"))
    )
    (comp (ref "U100")
      (value "AD7291")
      (footprint "eagle-import:QFN-20-4040")
      (fields (field (name "SKU") "27-0003"))
      (libsource (lib "eagle-import") (part "AD7291"))
    )
    (comp (ref "U101")
      (value "AD8515")
      (footprint "eagle-import:SOT23-5")
      (fields (field (name "SKU") "08-0002"))
      (libsource (lib "eagle-import") (part "OPAMP-1-AD8515"))
    )
    (comp (ref "U108")
      (value "AD7291")
      (footprint "eagle-import:QFN-20-4040")
      (fields (field (name "SKU") "27-0003"))
      (libsource (lib "eagle-import") (part "AD7291"))
    )
    (comp (ref "U109")
      (value "AD8515")
      (footprint "eagle-import:SOT23-5")
      (fields (field (name "SKU") "08-0002"))
      (libsource (lib "eagle-import") (part "OPAMP-1-AD8515"))
    )
    (comp (ref "C1")
      (value "100nF 10%")
      (footprint "eagle-import:1608")
      (fields
        (field (name "PACKAGE") "1608")
        (field (name "SKU") "11-104A")
        (field (name "TEMP") "X7R")
        (field (name "VOLTAGE") "50V")
      )
      (libsource (lib "eagle-import") (part "CAP-V-1608-100NF"))
    )
    (comp (ref "C2")
      (value "100nF 10%")
      (footprint "eagle-import:1608")
      (fields
        (field (name "PACKAGE") "1608")
        (field (name "SKU") "11-104A")
        (field (name "TEMP") "X7R")
        (field (name "VOLTAGE") "50V")
      )
      (libsource (lib "eagle-import") (part "CAP-V-1608-100NF"))
    )
    (comp (ref "C3")
      (value "100nF 10%")
      (footprint "eagle-import:1608")
      (fields
        (field (name "PACKAGE") "1608")
        (field (name "SKU") "11-104A")
        (field (name "TEMP") "X7R")
        (field (name "VOLTAGE") "50V")
      )
      (libsource (lib "eagle-import") (part "CAP-V-1608-100NF"))
    )
    (comp (ref "C4")
      (value "100nF 10%")
      (footprint "eagle-import:1608")
      (fields
        (field (name "PACKAGE") "1608")
        (field (name "SKU") "11-104A")
        (field (name "TEMP") "X7R")
        (field (name "VOLTAGE") "50V")
      )
      (libsource (lib "eagle-import") (part "CAP-V-1608-100NF"))
    )
    (comp (ref "C113")
      (value "100nF 10%")
      (footprint "eagle-import:1608")
      (fields
        (field (name "PACKAGE") "1608")
        (field (name "SKU") "11-104A")
        (field (name "TEMP") "X7R")
        (field (name "VOLTAGE") "50V")
      )
      (libsource (lib "eagle-import") (part "CAP-V-1608-100NF"))
    )
    (comp (ref "C121")
      (value "100nF 10%")
      (footprint "eagle-import:1608")
      (fields
        (field (name "PACKAGE") "1608")
        (field (name "SKU") "11-104A")
        (field (name "TEMP") "X7R")
        (field (name "VOLTAGE") "50V")
      )
      (libsource (lib "eagle-import") (part "CAP-V-1608-100NF"))
    )
    (comp (ref "H1")
      (value "M3")
      (footprint "eagle-import:MOUNTING_HOLE-3.3")
      (fields (field (name "SKU") "48-004x"))
      (libsource (lib "eagle-import") (part "MOUNTING_HOLE-3.3"))
    )
    (comp (ref "H2")
      (value "M3")
      (footprint "eagle-import:MOUNTING_HOLE-3.3")
      (fields (field (name "SKU") "48-004x"))
      (libsource (lib "eagle-import") (part "MOUNTING_HOLE-3.3"))
    )
    (comp (ref "H3")
      (value "M3")
      (footprint "eagle-import:MOUNTING_HOLE-3.3")
      (fields (field (name "SKU") "48-004x"))
      (libsource (lib "eagle-import") (part "MOUNTING_HOLE-3.3"))
    )
    (comp (ref "H4")
      (value "M3")
      (footprint "eagle-import:MOUNTING_HOLE-3.3")
      (fields (field (name "SKU") "48-004x"))
      (libsource (lib "eagle-import") (part "MOUNTING_HOLE-3.3"))
    )
    (comp (ref "H5")
      (value "M3")
      (footprint "eagle-import:MOUNTING_HOLE-3.3")
      (fields (field (name "SKU") "48-004x"))
      (libsource (lib "eagle-import") (part "MOUNTING_HOLE-3.3"))
    )
    (comp (ref "H6")
      (value "M3")
      (footprint "eagle-import:MOUNTING_HOLE-3.3")
      (fields (field (name "SKU") "48-004x"))
      (libsource (lib "eagle-import") (part "MOUNTING_HOLE-3.3"))
    )
    (comp (ref "LOGO1")
      (value "SIGNATUREHENDRIK")
      (footprint "eagle-import:SIGN-HENDRIK")
      (libsource (lib "eagle-import") (part "SIGNATUREHENDRIK"))
    )
    (comp (ref "LOGO100")
      (value "Satellite 16mm")
      (footprint "eagle-import:CIS-SATELLITE-16")
      (libsource (lib "eagle-import") (part "CIS-LOGO-SATELLITE-16MM"))
    )
    (comp (ref "R1")
      (value "0Ω <20mΩ")
      (footprint "eagle-import:1608")
      (fields
        (field (name "PACKAGE") "1608")
        (field (name "POWER") "1/10W")
        (field (name "SKU") "21-0000")
        (field (name "TEMP") "70°C Max 2A")
      )
      (libsource (lib "eagle-import") (part "RES-V-1608-0"))
    )
    (comp (ref "R2")
      (value "0Ω <20mΩ")
      (footprint "eagle-import:1608")
      (fields
        (field (name "PACKAGE") "1608")
        (field (name "POWER") "1/10W")
        (field (name "SKU") "21-0000")
        (field (name "TEMP") "70°C Max 2A")
      )
      (libsource (lib "eagle-import") (part "RES-V-1608-0"))
    )
    (comp (ref "R9")
      (value "0Ω <20mΩ")
      (footprint "eagle-import:1608")
      (fields
        (field (name "PACKAGE") "1608")
        (field (name "POWER") "1/10W")
        (field (name "SKU") "21-0000")
        (field (name "TEMP") "70°C Max 2A")
      )
      (libsource (lib "eagle-import") (part "RES-V-1608-0"))
    )
    (comp (ref "R10")
      (value "0Ω <20mΩ")
      (footprint "eagle-import:1608")
      (fields
        (field (name "PACKAGE") "1608")
        (field (name "POWER") "1/10W")
        (field (name "SKU") "21-0000")
        (field (name "TEMP") "70°C Max 2A")
      )
      (libsource (lib "eagle-import") (part "RES-V-1608-0"))
    )
    (comp (ref "R120")
      (value "0Ω <20mΩ")
      (footprint "eagle-import:1608")
      (fields
        (field (name "PACKAGE") "1608")
        (field (name "POWER") "1/10W")
        (field (name "SKU") "21-0000")
        (field (name "TEMP") "70°C Max 2A")
      )
      (libsource (lib "eagle-import") (part "RES-V-1608-0"))
    )
    (comp (ref "R125")
      (value "0Ω <20mΩ")
      (footprint "eagle-import:1608")
      (fields
        (field (name "PACKAGE") "1608")
        (field (name "POWER") "1/10W")
        (field (name "SKU") "21-0000")
        (field (name "TEMP") "70°C Max 2A")
      )
      (libsource (lib "eagle-import") (part "RES-V-1608-0"))
    )
    (comp (ref "C100")
      (value "100nF 10%")
      (footprint "eagle-import:1608")
      (fields
        (field (name "PACKAGE") "1608")
        (field (name "SKU") "11-104A")
        (field (name "TEMP") "X7R")
        (field (name "VOLTAGE") "50V")
      )
      (libsource (lib "eagle-import") (part "CAP-V-1608-100NF"))
    )
    (comp (ref "C101")
      (value "4.7µF 10%")
      (footprint "eagle-import:4028-POL")
      (fields
        (field (name "ESR") "Max 900mΩ")
        (field (name "PACKAGE") "Tant-B")
        (field (name "SKU") "16-475A")
        (field (name "VOLTAGE") "20V")
      )
      (libsource (lib "eagle-import") (part "CAP-POL-V-4028-4.7UF"))
    )
    (comp (ref "D1")
      (value "SFH 2430")
      (footprint "eagle-import:SFH2430")
      (fields
        (field (name "SKU") "66-0003")
        (field (name "SENSITIVITY") "6.3nA/lx")
        (field (name "VR") "5V")
        (field (name "HALF_ANGLE") "±60°")
      )
      (libsource (lib "eagle-import") (part "PHOTODIODE-SFH2430"))
    )
    (comp (ref "FB100")
      (value "1.5kΩ @ 100MHz")
      (footprint "eagle-import:1608")
      (fields
        (field (name "CURRENT") "500mA")
        (field (name "DCR") "500mΩ")
        (field (name "PACKAGE") "1608")
        (field (name "SKU") "36-152A")
      )
      (libsource (lib "eagle-import") (part "CHOKE-H-1608-1.5K"))
    )
    (comp (ref "J100")
      (value "ADCS")
      (footprint "eagle-import:PICOLOCK1.5-04")
      (fields (field (name "SKU") "04-0001") (field (name "PACKAGE") "PicoLock"))
      (libsource (lib "eagle-import") (part "1X04-PICOLOCK"))
    )
    (comp (ref "J101")
      (value "EPS")
      (footprint "eagle-import:PICOLOCK1.5-07")
      (fields (field (name "SKU") "04-0007") (field (name "PACKAGE") "PicoLock"))
      (libsource (lib "eagle-import") (part "1X07-PICOLOCK"))
    )
    (comp (ref "L100")
      (value "xxx Turns")
      (footprint "eagle-import:SMD-3030-2")
      (fields (field (name "AREA") "xxx mm²") (field (name "DCR") "xxΩ x%") (field (name "SKU") "67-0001"))
      (libsource (lib "eagle-import") (part "MAGNETORQUER-SMD-3030-1UPV"))
    )
    (comp (ref "R3")
      (value "10kΩ 0.1%")
      (footprint "eagle-import:1608")
      (fields
        (field (name "PACKAGE") "1608")
        (field (name "POWER") "1/8W")
        (field (name "SKU") "21-1002")
        (field (name "TEMP") "25ppm/°C")
      )
      (libsource (lib "eagle-import") (part "RES-V-1608-10K"))
    )
    (comp (ref "R4")
      (value "10kΩ 0.1%")
      (footprint "eagle-import:1608")
      (fields
        (field (name "PACKAGE") "1608")
        (field (name "POWER") "1/8W")
        (field (name "SKU") "21-1002")
        (field (name "TEMP") "25ppm/°C")
      )
      (libsource (lib "eagle-import") (part "RES-V-1608-10K"))
    )
    (comp (ref "R5")
      (value "10kΩ 0.1%")
      (footprint "eagle-import:1608")
      (fields
        (field (name "PACKAGE") "1608")
        (field (name "POWER") "1/8W")
        (field (name "SKU") "21-1002")
        (field (name "TEMP") "25ppm/°C")
      )
      (libsource (lib "eagle-import") (part "RES-V-1608-10K"))
    )
    (comp (ref "R6")
      (value "1.2kΩ 0.1%")
      (footprint "eagle-import:1608")
      (fields
        (field (name "PACKAGE") "1608")
        (field (name "POWER") "1/5W")
        (field (name "SKU") "21-1201")
        (field (name "TEMP") "50ppm/°C")
      )
      (libsource (lib "eagle-import") (part "RES-V-1608-1.2K"))
    )
    (comp (ref "R7")
      (value "10kΩ 0.1%")
      (footprint "eagle-import:1608")
      (fields
        (field (name "PACKAGE") "1608")
        (field (name "POWER") "1/8W")
        (field (name "SKU") "21-1002")
        (field (name "TEMP") "25ppm/°C")
      )
      (libsource (lib "eagle-import") (part "RES-V-1608-10K"))
    )
    (comp (ref "R8")
      (value "10kΩ 0.1%")
      (footprint "eagle-import:1608")
      (fields
        (field (name "PACKAGE") "1608")
        (field (name "POWER") "1/8W")
        (field (name "SKU") "21-1002")
        (field (name "TEMP") "25ppm/°C")
      )
      (libsource (lib "eagle-import") (part "RES-V-1608-10K"))
    )
    (comp (ref "R100")
      (value "2.2kΩ 1%")
      (footprint "eagle-import:1608")
      (fields
        (field (name "PACKAGE") "1608")
        (field (name "POWER") "1/10W")
        (field (name "SKU") "21-2201")
        (field (name "TEMP") "100ppm/°C")
      )
      (libsource (lib "eagle-import") (part "RES-V-1608-2.2K"))
    )
    (comp (ref "R101")
      (value "2.2kΩ 1%")
      (footprint "eagle-import:1608")
      (fields
        (field (name "PACKAGE") "1608")
        (field (name "POWER") "1/10W")
        (field (name "SKU") "21-2201")
        (field (name "TEMP") "100ppm/°C")
      )
      (libsource (lib "eagle-import") (part "RES-V-1608-2.2K"))
    )
    (comp (ref "R102")
      (value "10kΩ 0.1%")
      (footprint "eagle-import:1608")
      (fields
        (field (name "PACKAGE") "1608")
        (field (name "POWER") "1/8W")
        (field (name "SKU") "21-1002")
        (field (name "TEMP") "25ppm/°C")
      )
      (libsource (lib "eagle-import") (part "RES-V-1608-10K"))
    )
    (comp (ref "R103")
      (value "2.2kΩ 1%")
      (footprint "eagle-import:1608")
      (fields
        (field (name "PACKAGE") "1608")
        (field (name "POWER") "1/10W")
        (field (name "SKU") "21-2201")
        (field (name "TEMP") "100ppm/°C")
      )
      (libsource (lib "eagle-import") (part "RES-V-1608-2.2K"))
    )
    (comp (ref "R104")
      (value "2.2kΩ 1%")
      (footprint "eagle-import:1608")
      (fields
        (field (name "PACKAGE") "1608")
        (field (name "POWER") "1/10W")
        (field (name "SKU") "21-2201")
        (field (name "TEMP") "100ppm/°C")
      )
      (libsource (lib "eagle-import") (part "RES-V-1608-2.2K"))
    )
    (comp (ref "R143")
      (value "10kΩ 0.1%")
      (footprint "eagle-import:1608")
      (fields
        (field (name "PACKAGE") "1608")
        (field (name "POWER") "1/8W")
        (field (name "SKU") "21-1002")
        (field (name "TEMP") "25ppm/°C")
      )
      (libsource (lib "eagle-import") (part "RES-V-1608-10K"))
    )
    (comp (ref "RT1")
      (value "10kΩ 5%")
      (footprint "eagle-import:1608")
      (fields
        (field (name "B2585") "3960K 1%")
        (field (name "PACKAGE") "1608")
        (field (name "SKU") "26-0008")
      )
      (libsource (lib "eagle-import") (part "THERMISTOR-V-1608-10K"))
    )
    (comp (ref "RT2")
      (value "10kΩ 5%")
      (footprint "eagle-import:1608")
      (fields
        (field (name "B2585") "3960K 1%")
        (field (name "PACKAGE") "1608")
        (field (name "SKU") "26-0008")
      )
      (libsource (lib "eagle-import") (part "THERMISTOR-V-1608-10K"))
    )
    (comp (ref "RT3")
      (value "10kΩ 5%")
      (footprint "eagle-import:1608")
      (fields
        (field (name "B2585") "3960K 1%")
        (field (name "PACKAGE") "1608")
        (field (name "SKU") "26-0008")
      )
      (libsource (lib "eagle-import") (part "THERMISTOR-V-1608-10K"))
    )
    (comp (ref "RT4")
      (value "10kΩ 5%")
      (footprint "eagle-import:1608")
      (fields
        (field (name "B2585") "3960K 1%")
        (field (name "PACKAGE") "1608")
        (field (name "SKU") "26-0008")
      )
      (libsource (lib "eagle-import") (part "THERMISTOR-V-1608-10K"))
    )
    (comp (ref "RT5")
      (value "10kΩ 5%")
      (footprint "eagle-import:1608")
      (fields
        (field (name "B2585") "3960K 1%")
        (field (name "PACKAGE") "1608")
        (field (name "SKU") "26-0008")
      )
      (libsource (lib "eagle-import") (part "THERMISTOR-V-1608-10K"))
    )
    (comp (ref "RT100")
      (value "10kΩ 5%")
      (footprint "eagle-import:1608")
      (fields
        (field (name "B2585") "3960K 1%")
        (field (name "PACKAGE") "1608")
        (field (name "SKU") "26-0008")
      )
      (libsource (lib "eagle-import") (part "THERMISTOR-V-1608-10K"))
    )
    (comp (ref "RT103")
      (value "10kΩ 5%")
      (footprint "eagle-import:1608")
      (fields
        (field (name "B2585") "3960K 1%")
        (field (name "PACKAGE") "1608")
        (field (name "SKU") "26-0008")
      )
      (libsource (lib "eagle-import") (part "THERMISTOR-V-1608-10K"))
    )
    (comp (ref "TP100")
      (value "TEST_POINT-SMD-C-1.25")
      (footprint "eagle-import:SMD-C-1.25")
      (libsource (lib "eagle-import") (part "TEST_POINT-SMD-C-1.25"))
    )
  )
  (nets
    (net (code "1") (name "3.3V") (class "Default")
      (node (ref "C105") (pin "1") (pinfunction "1_1") (pintype "passive"))
      (node (ref "C122") (pin "1") (pinfunction "1_1") (pintype "passive"))
      (node (ref "D1") (pin "C") (pinfunction "C_C") (pintype "passive"))
      (node (ref "FB100") (pin "1") (pinfunction "1_1") (pintype "passive"))
      (node (ref "J101") (pin "1") (pinfunction "1_1") (pintype "passive"))
      (node (ref "R100") (pin "2") (pinfunction "2_2") (pintype "passive"))
      (node (ref "R101") (pin "2") (pinfunction "2_2") (pintype "passive"))
      (node (ref "R103") (pin "2") (pinfunction "2_2") (pintype "passive"))
      (node (ref "R104") (pin "2") (pinfunction "2_2") (pintype "passive"))
      (node (ref "R109") (pin "2") (pinfunction "2_2") (pintype "passive"))
      (node (ref "R110") (pin "2") (pinfunction "2_2") (pintype "passive"))
      (node (ref "R133") (pin "2") (pinfunction "2_2") (pintype "passive"))
      (node (ref "R134") (pin "2") (pinfunction "2_2") (pintype "passive"))
      (node (ref "U100") (pin "16") (pinfunction "VDRIVE_16") (pintype "power_in"))
      (node (ref "U100") (pin "17") (pinfunction "~{PD}/~{RST}_17") (pintype "input"))
      (node (ref "U108") (pin "16") (pinfunction "VDRIVE_16") (pintype "power_in"))
      (node (ref "U108") (pin "17") (pinfunction "~{PD}/~{RST}_17") (pintype "input"))
    )
    (net (code "2") (name "AGND") (class "Default")
      (node (ref "C100") (pin "2") (pinfunction "2_2") (pintype "passive"))
      (node (ref "C101") (pin "C") (pinfunction "C_C") (pintype "passive"))
      (node (ref "C102") (pin "2") (pinfunction "2_2") (pintype "passive"))
      (node (ref "C103") (pin "2") (pinfunction "2_2") (pintype "passive"))
      (node (ref "C104") (pin "2") (pinfunction "2_2") (pintype "passive"))
      (node (ref "C106") (pin "2") (pinfunction "2_2") (pintype "passive"))
      (node (ref "C124") (pin "2") (pinfunction "2_2") (pintype "passive"))
      (node (ref "C125") (pin "2") (pinfunction "2_2") (pintype "passive"))
      (node (ref "C126") (pin "2") (pinfunction "2_2") (pintype "passive"))
      (node (ref "C127") (pin "2") (pinfunction "2_2") (pintype "passive"))
      (node (ref "R107") (pin "1") (pinfunction "1_1") (pintype "passive"))
      (node (ref "R107") (pin "2") (pinfunction "2_2") (pintype "passive"))
      (node (ref "R123") (pin "1") (pinfunction "1_1") (pintype "passive"))
      (node (ref "R138") (pin "1") (pinfunction "1_1") (pintype "passive"))
      (node (ref "R138") (pin "2") (pinfunction "2_2") (pintype "passive"))
      (node (ref "R6") (pin "1") (pinfunction "1_1") (pintype "passive"))
      (node (ref "RN100") (pin "1") (pinfunction "A1_1") (pintype "passive"))
      (node (ref "RN101") (pin "1") (pinfunction "A1_1") (pintype "passive"))
      (node (ref "RT1") (pin "1") (pinfunction "1_1") (pintype "passive"))
      (node (ref "RT100") (pin "1") (pinfunction "1_1") (pintype "passive"))
      (node (ref "RT101") (pin "2") (pinfunction "2_2") (pintype "passive"))
      (node (ref "RT102") (pin "2") (pinfunction "2_2") (pintype "passive"))
      (node (ref "RT103") (pin "1") (pinfunction "1_1") (pintype "passive"))
      (node (ref "RT2") (pin "1") (pinfunction "1_1") (pintype "passive"))
      (node (ref "RT3") (pin "1") (pinfunction "1_1") (pintype "passive"))
      (node (ref "RT4") (pin "1") (pinfunction "1_1") (pintype "passive"))
      (node (ref "RT5") (pin "1") (pinfunction "1_1") (pintype "passive"))
      (node (ref "U100") (pin "6") (pinfunction "AGND_6") (pintype "power_in"))
      (node (ref "U101") (pin "2") (pinfunction "V-_2") (pintype "power_in"))
      (node (ref "U102") (pin "1") (pinfunction "REF_1") (pintype "input"))
      (node (ref "U102") (pin "2") (pinfunction "GND_2") (pintype "power_in"))
      (node (ref "U104") (pin "1") (pinfunction "REF_1") (pintype "input"))
      (node (ref "U104") (pin "2") (pinfunction "GND_2") (pintype "power_in"))
      (node (ref "U106") (pin "1") (pinfunction "REF_1") (pintype "input"))
      (node (ref "U106") (pin "2") (pinfunction "GND_2") (pintype "power_in"))
      (node (ref "U107") (pin "1") (pinfunction "REF_1") (pintype "input"))
      (node (ref "U107") (pin "2") (pinfunction "GND_2") (pintype "power_in"))
      (node (ref "U108") (pin "6") (pinfunction "AGND_6") (pintype "power_in"))
      (node (ref "U109") (pin "2") (pinfunction "V-_2") (pintype "power_in"))
    )
    (net (code "3") (name "AVDD") (class "Default")
      (node (ref "C100") (pin "1") (pinfunction "1_1") (pintype "passive"))
      (node (ref "C101") (pin "A") (pinfunction "A_A") (pintype "passive"))
      (node (ref "C104") (pin "1") (pinfunction "1_1") (pintype "passive"))
      (node (ref "C106") (pin "1") (pinfunction "1_1") (pintype "passive"))
      (node (ref "C125") (pin "1") (pinfunction "1_1") (pintype "passive"))
      (node (ref "C127") (pin "1") (pinfunction "1_1") (pintype "passive"))
      (node (ref "FB100") (pin "2") (pinfunction "2_2") (pintype "passive"))
      (node (ref "R105") (pin "1") (pinfunction "1_1") (pintype "passive"))
      (node (ref "R105") (pin "2") (pinfunction "2_2") (pintype "passive"))
      (node (ref "R108") (pin "1") (pinfunction "1_1") (pintype "passive"))
      (node (ref "R108") (pin "2") (pinfunction "2_2") (pintype "passive"))
      (node (ref "TP100") (pin "1") (pinfunction "1_1") (pintype "passive"))
      (node (ref "U100") (pin "10") (pinfunction "VDD_10") (pintype "power_in"))
      (node (ref "U101") (pin "5") (pinfunction "V+_5") (pintype "power_in"))
      (node (ref "U102") (pin "3") (pinfunction "VDD_3") (pintype "power_in"))
      (node (ref "U104") (pin "3") (pinfunction "VDD_3") (pintype "power_in"))
      (node (ref "U106") (pin "3") (pinfunction "VDD_3") (pintype "power_in"))
      (node (ref "U107") (pin "3") (pinfunction "VDD_3") (pintype "power_in"))
      (node (ref "U108") (pin "10") (pinfunction "VDD_10") (pintype "power_in"))
      (node (ref "U109") (pin "5") (pinfunction "V+_5") (pintype "power_in"))
    )
    (net (code "4") (name "AVREF-0") (class "Default")
      (node (ref "R139") (pin "2") (pinfunction "2_2") (pintype "passive"))
      (node (ref "R140") (pin "2") (pinfunction "2_2") (pintype "passive"))
      (node (ref "R141") (pin "2") (pinfunction "2_2") (pintype "passive"))
      (node (ref "TP102") (pin "1") (pinfunction "1_1") (pintype "passive"))
    )
    (net (code "5") (name "AVREF-1") (class "Default")
      (node (ref "R102") (pin "2") (pinfunction "2_2") (pintype "passive"))
      (node (ref "R143") (pin "2") (pinfunction "2_2") (pintype "passive"))
      (node (ref "R3") (pin "2") (pinfunction "2_2") (pintype "passive"))
      (node (ref "R4") (pin "2") (pinfunction "2_2") (pintype "passive"))
      (node (ref "R5") (pin "2") (pinfunction "2_2") (pintype "passive"))
      (node (ref "R7") (pin "2") (pinfunction "2_2") (pintype "passive"))
      (node (ref "R8") (pin "2") (pinfunction "2_2") (pintype "passive"))
      (node (ref "TP101") (pin "1") (pinfunction "1_1") (pintype "passive"))
      (node (ref "U101") (pin "1") (pinfunction "OUT_1") (pintype "output"))
      (node (ref "U101") (pin "4") (pinfunction "IN-_4") (pintype "passive"))
    )
    (net (code "6") (name "CHASSIS") (class "Default")
      (node (ref "C1") (pin "1") (pinfunction "1_1") (pintype "passive"))
      (node (ref "C113") (pin "1") (pinfunction "1_1") (pintype "passive"))
      (node (ref "C121") (pin "1") (pinfunction "1_1") (pintype "passive"))
      (node (ref "C2") (pin "1") (pinfunction "1_1") (pintype "passive"))
      (node (ref "C3") (pin "1") (pinfunction "1_1") (pintype "passive"))
      (node (ref "C4") (pin "1") (pinfunction "1_1") (pintype "passive"))
      (node (ref "H1") (pin "1") (pinfunction "MOUNT_1") (pintype "passive"))
      (node (ref "H1") (pin "V1") (pinfunction "MOUNT_V1") (pintype "passive"))
      (node (ref "H1") (pin "V10") (pinfunction "MOUNT_V10") (pintype "passive"))
      (node (ref "H1") (pin "V2") (pinfunction "MOUNT_V2") (pintype "passive"))
      (node (ref "H1") (pin "V3") (pinfunction "MOUNT_V3") (pintype "passive"))
      (node (ref "H1") (pin "V4") (pinfunction "MOUNT_V4") (pintype "passive"))
      (node (ref "H1") (pin "V5") (pinfunction "MOUNT_V5") (pintype "passive"))
      (node (ref "H1") (pin "V6") (pinfunction "MOUNT_V6") (pintype "passive"))
      (node (ref "H1") (pin "V7") (pinfunction "MOUNT_V7") (pintype "passive"))
      (node (ref "H1") (pin "V8") (pinfunction "MOUNT_V8") (pintype "passive"))
      (node (ref "H1") (pin "V9") (pinfunction "MOUNT_V9") (pintype "passive"))
      (node (ref "H2") (pin "1") (pinfunction "MOUNT_1") (pintype "passive"))
      (node (ref "H2") (pin "V1") (pinfunction "MOUNT_V1") (pintype "passive"))
      (node (ref "H2") (pin "V10") (pinfunction "MOUNT_V10") (pintype "passive"))
      (node (ref "H2") (pin "V2") (pinfunction "MOUNT_V2") (pintype "passive"))
      (node (ref "H2") (pin "V3") (pinfunction "MOUNT_V3") (pintype "passive"))
      (node (ref "H2") (pin "V4") (pinfunction "MOUNT_V4") (pintype "passive"))
      (node (ref "H2") (pin "V5") (pinfunction "MOUNT_V5") (pintype "passive"))
      (node (ref "H2") (pin "V6") (pinfunction "MOUNT_V6") (pintype "passive"))
      (node (ref "H2") (pin "V7") (pinfunction "MOUNT_V7") (pintype "passive"))
      (node (ref "H2") (pin "V8") (pinfunction "MOUNT_V8") (pintype "passive"))
      (node (ref "H2") (pin "V9") (pinfunction "MOUNT_V9") (pintype "passive"))
      (node (ref "H3") (pin "1") (pinfunction "MOUNT_1") (pintype "passive"))
      (node (ref "H3") (pin "V1") (pinfunction "MOUNT_V1") (pintype "passive"))
      (node (ref "H3") (pin "V10") (pinfunction "MOUNT_V10") (pintype "passive"))
      (node (ref "H3") (pin "V2") (pinfunction "MOUNT_V2") (pintype "passive"))
      (node (ref "H3") (pin "V3") (pinfunction "MOUNT_V3") (pintype "passive"))
      (node (ref "H3") (pin "V4") (pinfunction "MOUNT_V4") (pintype "passive"))
      (node (ref "H3") (pin "V5") (pinfunction "MOUNT_V5") (pintype "passive"))
      (node (ref "H3") (pin "V6") (pinfunction "MOUNT_V6") (pintype "passive"))
      (node (ref "H3") (pin "V7") (pinfunction "MOUNT_V7") (pintype "passive"))
      (node (ref "H3") (pin "V8") (pinfunction "MOUNT_V8") (pintype "passive"))
      (node (ref "H3") (pin "V9") (pinfunction "MOUNT_V9") (pintype "passive"))
      (node (ref "H4") (pin "1") (pinfunction "MOUNT_1") (pintype "passive"))
      (node (ref "H4") (pin "V1") (pinfunction "MOUNT_V1") (pintype "passive"))
      (node (ref "H4") (pin "V10") (pinfunction "MOUNT_V10") (pintype "passive"))
      (node (ref "H4") (pin "V2") (pinfunction "MOUNT_V2") (pintype "passive"))
      (node (ref "H4") (pin "V3") (pinfunction "MOUNT_V3") (pintype "passive"))
      (node (ref "H4") (pin "V4") (pinfunction "MOUNT_V4") (pintype "passive"))
      (node (ref "H4") (pin "V5") (pinfunction "MOUNT_V5") (pintype "passive"))
      (node (ref "H4") (pin "V6") (pinfunction "MOUNT_V6") (pintype "passive"))
      (node (ref "H4") (pin "V7") (pinfunction "MOUNT_V7") (pintype "passive"))
      (node (ref "H4") (pin "V8") (pinfunction "MOUNT_V8") (pintype "passive"))
      (node (ref "H4") (pin "V9") (pinfunction "MOUNT_V9") (pintype "passive"))
      (node (ref "H5") (pin "1") (pinfunction "MOUNT_1") (pintype "passive"))
      (node (ref "H5") (pin "V1") (pinfunction "MOUNT_V1") (pintype "passive"))
      (node (ref "H5") (pin "V10") (pinfunction "MOUNT_V10") (pintype "passive"))
      (node (ref "H5") (pin "V2") (pinfunction "MOUNT_V2") (pintype "passive"))
      (node (ref "H5") (pin "V3") (pinfunction "MOUNT_V3") (pintype "passive"))
      (node (ref "H5") (pin "V4") (pinfunction "MOUNT_V4") (pintype "passive"))
      (node (ref "H5") (pin "V5") (pinfunction "MOUNT_V5") (pintype "passive"))
      (node (ref "H5") (pin "V6") (pinfunction "MOUNT_V6") (pintype "passive"))
      (node (ref "H5") (pin "V7") (pinfunction "MOUNT_V7") (pintype "passive"))
      (node (ref "H5") (pin "V8") (pinfunction "MOUNT_V8") (pintype "passive"))
      (node (ref "H5") (pin "V9") (pinfunction "MOUNT_V9") (pintype "passive"))
      (node (ref "H6") (pin "1") (pinfunction "MOUNT_1") (pintype "passive"))
      (node (ref "H6") (pin "V1") (pinfunction "MOUNT_V1") (pintype "passive"))
      (node (ref "H6") (pin "V10") (pinfunction "MOUNT_V10") (pintype "passive"))
      (node (ref "H6") (pin "V2") (pinfunction "MOUNT_V2") (pintype "passive"))
      (node (ref "H6") (pin "V3") (pinfunction "MOUNT_V3") (pintype "passive"))
      (node (ref "H6") (pin "V4") (pinfunction "MOUNT_V4") (pintype "passive"))
      (node (ref "H6") (pin "V5") (pinfunction "MOUNT_V5") (pintype "passive"))
      (node (ref "H6") (pin "V6") (pinfunction "MOUNT_V6") (pintype "passive"))
      (node (ref "H6") (pin "V7") (pinfunction "MOUNT_V7") (pintype "passive"))
      (node (ref "H6") (pin "V8") (pinfunction "MOUNT_V8") (pintype "passive"))
      (node (ref "H6") (pin "V9") (pinfunction "MOUNT_V9") (pintype "passive"))
      (node (ref "R1") (pin "2") (pinfunction "2_2") (pintype "passive"))
      (node (ref "R10") (pin "2") (pinfunction "2_2") (pintype "passive"))
      (node (ref "R120") (pin "2") (pinfunction "2_2") (pintype "passive"))
      (node (ref "R125") (pin "2") (pinfunction "2_2") (pintype "passive"))
      (node (ref "R2") (pin "2") (pinfunction "2_2") (pintype "passive"))
      (node (ref "R9") (pin "2") (pinfunction "2_2") (pintype "passive"))
    )
    (net (code "7") (name "DGND") (class "Default")
      (node (ref "C105") (pin "2") (pinfunction "2_2") (pintype "passive"))
      (node (ref "C122") (pin "2") (pinfunction "2_2") (pintype "passive"))
      (node (ref "R111") (pin "1") (pinfunction "1_1") (pintype "passive"))
      (node (ref "R112") (pin "1") (pinfunction "1_1") (pintype "passive"))
      (node (ref "R122") (pin "1") (pinfunction "1_1") (pintype "passive"))
      (node (ref "R123") (pin "2") (pinfunction "2_2") (pintype "passive"))
      (node (ref "R131") (pin "1") (pinfunction "1_1") (pintype "passive"))
      (node (ref "R132") (pin "1") (pinfunction "1_1") (pintype "passive"))
      (node (ref "U100") (pin "9") (pinfunction "DGND_9") (pintype "power_in"))
      (node (ref "U100") (pin "PAD") (pinfunction "DGND_PAD") (pintype "power_in"))
      (node (ref "U108") (pin "9") (pinfunction "DGND_9") (pintype "power_in"))
      (node (ref "U108") (pin "PAD") (pinfunction "DGND_PAD") (pintype "power_in"))
    )
    (net (code "8") (name "I2C_SCL_ADCS") (class "Default")
      (node (ref "J100") (pin "2") (pinfunction "2_2") (pintype "passive"))
      (node (ref "R103") (pin "1") (pinfunction "1_1") (pintype "passive"))
      (node (ref "U100") (pin "15") (pinfunction "SCL_15") (pintype "input"))
    )
    (net (code "9") (name "I2C_SCL_PMIC") (class "Default")
      (node (ref "J101") (pin "3") (pinfunction "3_3") (pintype "passive"))
      (node (ref "R101") (pin "1") (pinfunction "1_1") (pintype "passive"))
      (node (ref "U108") (pin "15") (pinfunction "SCL_15") (pintype "input"))
    )
    (net (code "10") (name "I2C_SDA_ADCS") (class "Default")
      (node (ref "J100") (pin "1") (pinfunction "1_1") (pintype "passive"))
      (node (ref "R104") (pin "1") (pinfunction "1_1") (pintype "passive"))
      (node (ref "U100") (pin "14") (pinfunction "SDA_14") (pintype "bidirectional"))
    )
    (net (code "11") (name "I2C_SDA_PMIC") (class "Default")
      (node (ref "J101") (pin "2") (pinfunction "2_2") (pintype "passive"))
      (node (ref "R100") (pin "1") (pinfunction "1_1") (pintype "passive"))
      (node (ref "U108") (pin "14") (pinfunction "SDA_14") (pintype "bidirectional"))
    )
    (net (code "12") (name "I_OUT-A") (class "Default")
      (node (ref "U102") (pin "6") (pinfunction "OUT_6") (pintype "output"))
      (node (ref "U108") (pin "19") (pinfunction "IN1_19") (pintype "input"))
    )
    (net (code "13") (name "I_OUT-B") (class "Default")
      (node (ref "U107") (pin "6") (pinfunction "OUT_6") (pintype "output"))
      (node (ref "U108") (pin "5") (pinfunction "IN7_5") (pintype "input"))
    )
    (net (code "14") (name "Net-(C108-Pad2)") (class "Default")
      (node (ref "C108") (pin "2") (pinfunction "2_2") (pintype "passive"))
      (node (ref "C109") (pin "1") (pinfunction "1_1") (pintype "passive"))
    )
    (net (code "15") (name "Net-(C111-Pad1)") (class "Default")
      (node (ref "C111") (pin "1") (pinfunction "1_1") (pintype "passive"))
      (node (ref "L101") (pin "1") (pinfunction "1_1") (pintype "passive"))
      (node (ref "R106") (pin "2") (pinfunction "2_2") (pintype "passive"))
      (node (ref "R119") (pin "2") (pinfunction "2_2") (pintype "passive"))
    )
    (net (code "16") (name "Net-(C111-Pad2)") (class "Default")
      (node (ref "C111") (pin "2") (pinfunction "2_2") (pintype "passive"))
      (node (ref "C114") (pin "1") (pinfunction "1_1") (pintype "passive"))
    )
    (net (code "17") (name "Net-(C116-Pad1)") (class "Default")
      (node (ref "C116") (pin "1") (pinfunction "1_1") (pintype "passive"))
      (node (ref "C117") (pin "2") (pinfunction "2_2") (pintype "passive"))
    )
    (net (code "18") (name "Net-(C117-Pad1)") (class "Default")
      (node (ref "C117") (pin "1") (pinfunction "1_1") (pintype "passive"))
      (node (ref "L102") (pin "1") (pinfunction "1_1") (pintype "passive"))
      (node (ref "R126") (pin "2") (pinfunction "2_2") (pintype "passive"))
      (node (ref "R135") (pin "2") (pinfunction "2_2") (pintype "passive"))
    )
    (net (code "19") (name "Net-(C119-Pad1)") (class "Default")
      (node (ref "C119") (pin "1") (pinfunction "1_1") (pintype "passive"))
      (node (ref "C123") (pin "2") (pinfunction "2_2") (pintype "passive"))
    )
    (net (code "20") (name "Net-(J100-Pad3)") (class "Default")
      (node (ref "J100") (pin "3") (pinfunction "3_3") (pintype "passive"))
      (node (ref "L100") (pin "1") (pinfunction "1_1") (pintype "passive"))
    )
    (net (code "21") (name "Net-(J100-Pad4)") (class "Default")
      (node (ref "J100") (pin "4") (pinfunction "4_4") (pintype "passive"))
      (node (ref "L100") (pin "2") (pinfunction "2_2") (pintype "passive"))
    )
    (net (code "22") (name "Net-(R113-Pad1)") (class "Default")
      (node (ref "R113") (pin "1") (pinfunction "1_1") (pintype "passive"))
      (node (ref "R121") (pin "2") (pinfunction "2_2") (pintype "passive"))
    )
    (net (code "23") (name "Net-(R114-Pad2)") (class "Default")
      (node (ref "R114") (pin "2") (pinfunction "2_2") (pintype "passive"))
      (node (ref "R115") (pin "1") (pinfunction "1_1") (pintype "passive"))
    )
    (net (code "24") (name "Net-(R124-Pad2)") (class "Default")
      (node (ref "R124") (pin "2") (pinfunction "2_2") (pintype "passive"))
      (node (ref "R130") (pin "1") (pinfunction "1_1") (pintype "passive"))
    )
    (net (code "25") (name "Net-(R129-Pad2)") (class "Default")
      (node (ref "R129") (pin "2") (pinfunction "2_2") (pintype "passive"))
      (node (ref "R137") (pin "1") (pinfunction "1_1") (pintype "passive"))
    )
    (net (code "26") (name "Net-(RN101-B1)") (class "Default")
      (node (ref "R142") (pin "2") (pinfunction "2_2") (pintype "passive"))
      (node (ref "RN101") (pin "2") (pinfunction "B1_2") (pintype "passive"))
    )
    (net (code "27") (name "Net-(U100-AS0)") (class "Default")
      (node (ref "R110") (pin "1") (pinfunction "1_1") (pintype "passive"))
      (node (ref "R112") (pin "2") (pinfunction "2_2") (pintype "passive"))
      (node (ref "U100") (pin "11") (pinfunction "AS0_11") (pintype "passive"))
    )
    (net (code "28") (name "Net-(U100-AS1)") (class "Default")
      (node (ref "R109") (pin "1") (pinfunction "1_1") (pintype "passive"))
      (node (ref "R111") (pin "2") (pinfunction "2_2") (pintype "passive"))
      (node (ref "U100") (pin "13") (pinfunction "AS1_13") (pintype "passive"))
    )
    (net (code "29") (name "Net-(U100-DCAP)") (class "Default")
      (node (ref "C103") (pin "1") (pinfunction "1_1") (pintype "passive"))
      (node (ref "U100") (pin "8") (pinfunction "DCAP_8") (pintype "passive"))
    )
    (net (code "30") (name "Net-(U100-VREF)") (class "Default")
      (node (ref "C102") (pin "1") (pinfunction "1_1") (pintype "passive"))
      (node (ref "U100") (pin "7") (pinfunction "VREF_7") (pintype "bidirectional"))
      (node (ref "U101") (pin "3") (pinfunction "IN+_3") (pintype "passive"))
    )
    (net (code "31") (name "Net-(U102-IN+)") (class "Default")
      (node (ref "R116") (pin "1-KELVIN") (pinfunction "1-KELVIN_1-KELVIN") (pintype "passive"))
      (node (ref "U102") (pin "4") (pinfunction "IN+_4") (pintype "input"))
    )
    (net (code "32") (name "Net-(U102-IN-)") (class "Default")
      (node (ref "R116") (pin "2-KELVIN") (pinfunction "2-KELVIN_2-KELVIN") (pintype "passive"))
      (node (ref "U102") (pin "5") (pinfunction "IN-_5") (pintype "input"))
    )
    (net (code "33") (name "Net-(U103-ICTRL+)") (class "Default")
      (node (ref "R117") (pin "1") (pinfunction "1_1") (pintype "passive"))
      (node (ref "U103") (pin "6") (pinfunction "ICTRL-_6") (pintype "input"))
      (node (ref "U103") (pin "7") (pinfunction "ICTRL+_7") (pintype "input"))
    )
    (net (code "34") (name "Net-(U103-LX)") (class "Default")
      (node (ref "L101") (pin "2") (pinfunction "2_2") (pintype "passive"))
      (node (ref "U103") (pin "3") (pinfunction "LX_3") (pintype "input"))
    )
    (net (code "35") (name "Net-(U103-MPPT-SET)") (class "Default")
      (node (ref "C110") (pin "1") (pinfunction "1_1") (pintype "passive"))
      (node (ref "R106") (pin "1") (pinfunction "1_1") (pintype "passive"))
      (node (ref "R118") (pin "1") (pinfunction "1_1") (pintype "passive"))
      (node (ref "U103") (pin "1") (pinfunction "MPPT-SET_1") (pintype "input"))
    )
    (net (code "36") (name "Net-(U103-VCTRL)") (class "Default")
      (node (ref "C107") (pin "1") (pinfunction "1_1") (pintype "passive"))
      (node (ref "R113") (pin "2") (pinfunction "2_2") (pintype "passive"))
      (node (ref "R114") (pin "1") (pinfunction "1_1") (pintype "passive"))
      (node (ref "U103") (pin "5") (pinfunction "VCTRL_5") (pintype "input"))
    )
    (net (code "37") (name "Net-(U103-VOUT)") (class "Default")
      (node (ref "C108") (pin "1") (pinfunction "1_1") (pintype "passive"))
      (node (ref "D100") (pin "C") (pinfunction "C_C") (pintype "passive"))
      (node (ref "R116") (pin "1") (pinfunction "1_1") (pintype "passive"))
      (node (ref "R117") (pin "2") (pinfunction "2_2") (pintype "passive"))
      (node (ref "U103") (pin "4") (pinfunction "VOUT_4") (pintype "output"))
    )
    (net (code "38") (name "Net-(U103-X_SHUT)") (class "Default")
      (node (ref "R118") (pin "2") (pinfunction "2_2") (pintype "passive"))
      (node (ref "U103") (pin "8") (pinfunction "X_SHUT_8") (pintype "input"))
    )
    (net (code "39") (name "Net-(U104-IN+)") (class "Default")
      (node (ref "R119") (pin "1-KELVIN") (pinfunction "1-KELVIN_1-KELVIN") (pintype "passive"))
      (node (ref "U104") (pin "4") (pinfunction "IN+_4") (pintype "input"))
    )
    (net (code "40") (name "Net-(U104-IN-)") (class "Default")
      (node (ref "R119") (pin "2-KELVIN") (pinfunction "2-KELVIN_2-KELVIN") (pintype "passive"))
      (node (ref "U104") (pin "5") (pinfunction "IN-_5") (pintype "input"))
    )
    (net (code "41") (name "Net-(U105-ICTRL+)") (class "Default")
      (node (ref "R128") (pin "1") (pinfunction "1_1") (pintype "passive"))
      (node (ref "U105") (pin "6") (pinfunction "ICTRL-_6") (pintype "input"))
      (node (ref "U105") (pin "7") (pinfunction "ICTRL+_7") (pintype "input"))
    )
    (net (code "42") (name "Net-(U105-LX)") (class "Default")
      (node (ref "L102") (pin "2") (pinfunction "2_2") (pintype "passive"))
      (node (ref "U105") (pin "3") (pinfunction "LX_3") (pintype "input"))
    )
    (net (code "43") (name "Net-(U105-MPPT-SET)") (class "Default")
      (node (ref "C118") (pin "1") (pinfunction "1_1") (pintype "passive"))
      (node (ref "R127") (pin "1") (pinfunction "1_1") (pintype "passive"))
      (node (ref "R135") (pin "1") (pinfunction "1_1") (pintype "passive"))
      (node (ref "U105") (pin "1") (pinfunction "MPPT-SET_1") (pintype "input"))
    )
    (net (code "44") (name "Net-(U105-VCTRL)") (class "Default")
      (node (ref "C120") (pin "1") (pinfunction "1_1") (pintype "passive"))
      (node (ref "R129") (pin "1") (pinfunction "1_1") (pintype "passive"))
      (node (ref "R130") (pin "2") (pinfunction "2_2") (pintype "passive"))
      (node (ref "U105") (pin "5") (pinfunction "VCTRL_5") (pintype "input"))
    )
    (net (code "45") (name "Net-(U105-VOUT)") (class "Default")
      (node (ref "C123") (pin "1") (pinfunction "1_1") (pintype "passive"))
      (node (ref "D101") (pin "C") (pinfunction "C_C") (pintype "passive"))
      (node (ref "R128") (pin "2") (pinfunction "2_2") (pintype "passive"))
      (node (ref "R136") (pin "1") (pinfunction "1_1") (pintype "passive"))
      (node (ref "U105") (pin "4") (pinfunction "VOUT_4") (pintype "output"))
    )
    (net (code "46") (name "Net-(U105-X_SHUT)") (class "Default")
      (node (ref "R127") (pin "2") (pinfunction "2_2") (pintype "passive"))
      (node (ref "U105") (pin "8") (pinfunction "X_SHUT_8") (pintype "input"))
    )
    (net (code "47") (name "Net-(U106-IN+)") (class "Default")
      (node (ref "R126") (pin "1-KELVIN") (pinfunction "1-KELVIN_1-KELVIN") (pintype "passive"))
      (node (ref "U106") (pin "4") (pinfunction "IN+_4") (pintype "input"))
    )
    (net (code "48") (name "Net-(U106-IN-)") (class "Default")
      (node (ref "R126") (pin "2-KELVIN") (pinfunction "2-KELVIN_2-KELVIN") (pintype "passive"))
      (node (ref "U106") (pin "5") (pinfunction "IN-_5") (pintype "input"))
    )
    (net (code "49") (name "Net-(U107-IN+)") (class "Default")
      (node (ref "R136") (pin "1-KELVIN") (pinfunction "1-KELVIN_1-KELVIN") (pintype "passive"))
      (node (ref "U107") (pin "4") (pinfunction "IN+_4") (pintype "input"))
    )
    (net (code "50") (name "Net-(U107-IN-)") (class "Default")
      (node (ref "R136") (pin "2-KELVIN") (pinfunction "2-KELVIN_2-KELVIN") (pintype "passive"))
      (node (ref "U107") (pin "5") (pinfunction "IN-_5") (pintype "input"))
    )
    (net (code "51") (name "Net-(U108-AS0)") (class "Default")
      (node (ref "R132") (pin "2") (pinfunction "2_2") (pintype "passive"))
      (node (ref "R134") (pin "1") (pinfunction "1_1") (pintype "passive"))
      (node (ref "U108") (pin "11") (pinfunction "AS0_11") (pintype "passive"))
    )
    (net (code "52") (name "Net-(U108-AS1)") (class "Default")
      (node (ref "R131") (pin "2") (pinfunction "2_2") (pintype "passive"))
      (node (ref "R133") (pin "1") (pinfunction "1_1") (pintype "passive"))
      (node (ref "U108") (pin "13") (pinfunction "AS1_13") (pintype "passive"))
    )
    (net (code "53") (name "Net-(U108-DCAP)") (class "Default")
      (node (ref "C124") (pin "1") (pinfunction "1_1") (pintype "passive"))
      (node (ref "U108") (pin "8") (pinfunction "DCAP_8") (pintype "passive"))
    )
    (net (code "54") (name "Net-(U108-VREF)") (class "Default")
      (node (ref "C126") (pin "1") (pinfunction "1_1") (pintype "passive"))
      (node (ref "U108") (pin "7") (pinfunction "VREF_7") (pintype "bidirectional"))
      (node (ref "U109") (pin "3") (pinfunction "IN+_3") (pintype "passive"))
    )
    (net (code "55") (name "Net-(U109-IN-)") (class "Default")
      (node (ref "R141") (pin "1") (pinfunction "1_1") (pintype "passive"))
      (node (ref "U109") (pin "1") (pinfunction "OUT_1") (pintype "output"))
      (node (ref "U109") (pin "4") (pinfunction "IN-_4") (pintype "passive"))
    )
    (net (code "56") (name "PGND") (class "Default")
      (node (ref "C1") (pin "2") (pinfunction "2_2") (pintype "passive"))
      (node (ref "C107") (pin "2") (pinfunction "2_2") (pintype "passive"))
      (node (ref "C109") (pin "2") (pinfunction "2_2") (pintype "passive"))
      (node (ref "C110") (pin "2") (pinfunction "2_2") (pintype "passive"))
      (node (ref "C112") (pin "C") (pinfunction "C_C") (pintype "passive"))
      (node (ref "C113") (pin "2") (pinfunction "2_2") (pintype "passive"))
      (node (ref "C114") (pin "2") (pinfunction "2_2") (pintype "passive"))
      (node (ref "C115") (pin "C") (pinfunction "C_C") (pintype "passive"))
      (node (ref "C116") (pin "2") (pinfunction "2_2") (pintype "passive"))
      (node (ref "C118") (pin "2") (pinfunction "2_2") (pintype "passive"))
      (node (ref "C119") (pin "2") (pinfunction "2_2") (pintype "passive"))
      (node (ref "C120") (pin "2") (pinfunction "2_2") (pintype "passive"))
      (node (ref "C121") (pin "2") (pinfunction "2_2") (pintype "passive"))
      (node (ref "C2") (pin "2") (pinfunction "2_2") (pintype "passive"))
      (node (ref "C3") (pin "2") (pinfunction "2_2") (pintype "passive"))
      (node (ref "C4") (pin "2") (pinfunction "2_2") (pintype "passive"))
      (node (ref "D100") (pin "A") (pinfunction "A_A") (pintype "passive"))
      (node (ref "D101") (pin "A") (pinfunction "A_A") (pintype "passive"))
      (node (ref "J101") (pin "6") (pinfunction "6_6") (pintype "passive"))
      (node (ref "J101") (pin "7") (pinfunction "7_7") (pintype "passive"))
      (node (ref "PV1") (pin "VSS@1") (pinfunction "A_VSS@1") (pintype "passive"))
      (node (ref "PV1") (pin "VSS@2") (pinfunction "A_VSS@2") (pintype "passive"))
      (node (ref "PV1") (pin "VSS@3") (pinfunction "A_VSS@3") (pintype "passive"))
      (node (ref "PV2") (pin "VSS@1") (pinfunction "A_VSS@1") (pintype "passive"))
      (node (ref "PV2") (pin "VSS@2") (pinfunction "A_VSS@2") (pintype "passive"))
      (node (ref "PV2") (pin "VSS@3") (pinfunction "A_VSS@3") (pintype "passive"))
      (node (ref "R1") (pin "1") (pinfunction "1_1") (pintype "passive"))
      (node (ref "R10") (pin "1") (pinfunction "1_1") (pintype "passive"))
      (node (ref "R120") (pin "1") (pinfunction "1_1") (pintype "passive"))
      (node (ref "R121") (pin "1") (pinfunction "1_1") (pintype "passive"))
      (node (ref "R122") (pin "2") (pinfunction "2_2") (pintype "passive"))
      (node (ref "R124") (pin "1") (pinfunction "1_1") (pintype "passive"))
      (node (ref "R125") (pin "1") (pinfunction "1_1") (pintype "passive"))
      (node (ref "R2") (pin "1") (pinfunction "1_1") (pintype "passive"))
      (node (ref "R9") (pin "1") (pinfunction "1_1") (pintype "passive"))
      (node (ref "U103") (pin "2") (pinfunction "PGND_2") (pintype "power_in"))
      (node (ref "U105") (pin "2") (pinfunction "PGND_2") (pintype "power_in"))
    )
    (net (code "57") (name "PHOTODIODE") (class "Default")
      (node (ref "D1") (pin "A") (pinfunction "A_A") (pintype "passive"))
      (node (ref "R6") (pin "2") (pinfunction "2_2") (pintype "passive"))
      (node (ref "U100") (pin "18") (pinfunction "IN0_18") (pintype "input"))
    )
    (net (code "58") (name "PV_I-A") (class "Default")
      (node (ref "U104") (pin "6") (pinfunction "OUT_6") (pintype "output"))
      (node (ref "U108") (pin "18") (pinfunction "IN0_18") (pintype "input"))
    )
    (net (code "59") (name "PV_I-B") (class "Default")
      (node (ref "U106") (pin "6") (pinfunction "OUT_6") (pintype "output"))
      (node (ref "U108") (pin "4") (pinfunction "IN6_4") (pintype "input"))
    )
    (net (code "60") (name "PV_V-A") (class "Default")
      (node (ref "C112") (pin "A") (pinfunction "A_A") (pintype "passive"))
      (node (ref "PV2") (pin "VCC@1") (pinfunction "C_VCC@1") (pintype "passive"))
      (node (ref "PV2") (pin "VCC@2") (pinfunction "C_VCC@2") (pintype "passive"))
      (node (ref "PV2") (pin "VCC@3") (pinfunction "C_VCC@3") (pintype "passive"))
      (node (ref "PV2") (pin "VCC@4") (pinfunction "C_VCC@4") (pintype "passive"))
      (node (ref "R119") (pin "1") (pinfunction "1_1") (pintype "passive"))
      (node (ref "R142") (pin "1") (pinfunction "1_1") (pintype "passive"))
    )
    (net (code "61") (name "PV_V-B") (class "Default")
      (node (ref "C115") (pin "A") (pinfunction "A_A") (pintype "passive"))
      (node (ref "PV1") (pin "VCC@1") (pinfunction "C_VCC@1") (pintype "passive"))
      (node (ref "PV1") (pin "VCC@2") (pinfunction "C_VCC@2") (pintype "passive"))
      (node (ref "PV1") (pin "VCC@3") (pinfunction "C_VCC@3") (pintype "passive"))
      (node (ref "PV1") (pin "VCC@4") (pinfunction "C_VCC@4") (pintype "passive"))
      (node (ref "R126") (pin "1") (pinfunction "1_1") (pintype "passive"))
      (node (ref "RN100") (pin "2") (pinfunction "B1_2") (pintype "passive"))
    )
    (net (code "62") (name "PV_V_SENSE-A") (class "Default")
      (node (ref "RN101") (pin "3") (pinfunction "B2_3") (pintype "passive"))
      (node (ref "RN101") (pin "4") (pinfunction "A2_4") (pintype "passive"))
      (node (ref "U108") (pin "2") (pinfunction "IN4_2") (pintype "input"))
    )
    (net (code "63") (name "PV_V_SENSE-B") (class "Default")
      (node (ref "RN100") (pin "3") (pinfunction "B2_3") (pintype "passive"))
      (node (ref "RN100") (pin "4") (pinfunction "A2_4") (pintype "passive"))
      (node (ref "U108") (pin "3") (pinfunction "IN5_3") (pintype "input"))
    )
    (net (code "64") (name "TEMP-0") (class "Default")
      (node (ref "R5") (pin "1") (pinfunction "1_1") (pintype "passive"))
      (node (ref "RT3") (pin "2") (pinfunction "2_2") (pintype "passive"))
      (node (ref "U100") (pin "19") (pinfunction "IN1_19") (pintype "input"))
    )
    (net (code "65") (name "TEMP-1") (class "Default")
      (node (ref "R102") (pin "1") (pinfunction "1_1") (pintype "passive"))
      (node (ref "RT100") (pin "2") (pinfunction "2_2") (pintype "passive"))
      (node (ref "U100") (pin "20") (pinfunction "IN2_20") (pintype "input"))
    )
    (net (code "66") (name "TEMP-2") (class "Default")
      (node (ref "R7") (pin "1") (pinfunction "1_1") (pintype "passive"))
      (node (ref "RT4") (pin "2") (pinfunction "2_2") (pintype "passive"))
      (node (ref "U100") (pin "1") (pinfunction "IN3_1") (pintype "input"))
    )
    (net (code "67") (name "TEMP-3") (class "Default")
      (node (ref "R3") (pin "1") (pinfunction "1_1") (pintype "passive"))
      (node (ref "RT1") (pin "2") (pinfunction "2_2") (pintype "passive"))
      (node (ref "U100") (pin "2") (pinfunction "IN4_2") (pintype "input"))
    )
    (net (code "68") (name "TEMP-4") (class "Default")
      (node (ref "R143") (pin "1") (pinfunction "1_1") (pintype "passive"))
      (node (ref "RT103") (pin "2") (pinfunction "2_2") (pintype "passive"))
      (node (ref "U100") (pin "3") (pinfunction "IN5_3") (pintype "input"))
    )
    (net (code "69") (name "TEMP-5") (class "Default")
      (node (ref "R4") (pin "1") (pinfunction "1_1") (pintype "passive"))
      (node (ref "RT2") (pin "2") (pinfunction "2_2") (pintype "passive"))
      (node (ref "U100") (pin "4") (pinfunction "IN6_4") (pintype "input"))
    )
    (net (code "70") (name "TEMP-6") (class "Default")
      (node (ref "R8") (pin "1") (pinfunction "1_1") (pintype "passive"))
      (node (ref "RT5") (pin "2") (pinfunction "2_2") (pintype "passive"))
      (node (ref "U100") (pin "5") (pinfunction "IN7_5") (pintype "input"))
    )
    (net (code "71") (name "TEMP_MPPT-A") (class "Default")
      (node (ref "R139") (pin "1") (pinfunction "1_1") (pintype "passive"))
      (node (ref "RT101") (pin "1") (pinfunction "1_1") (pintype "passive"))
      (node (ref "U108") (pin "20") (pinfunction "IN2_20") (pintype "input"))
    )
    (net (code "72") (name "TEMP_MPPT-B") (class "Default")
      (node (ref "R140") (pin "1") (pinfunction "1_1") (pintype "passive"))
      (node (ref "RT102") (pin "1") (pinfunction "1_1") (pintype "passive"))
      (node (ref "U108") (pin "1") (pinfunction "IN3_1") (pintype "input"))
    )
    (net (code "73") (name "VOUT-A") (class "Default")
      (node (ref "J101") (pin "5") (pinfunction "5_5") (pintype "passive"))
      (node (ref "R115") (pin "2") (pinfunction "2_2") (pintype "passive"))
      (node (ref "R116") (pin "2") (pinfunction "2_2") (pintype "passive"))
    )
    (net (code "74") (name "VOUT-B") (class "Default")
      (node (ref "J101") (pin "4") (pinfunction "4_4") (pintype "passive"))
      (node (ref "R136") (pin "2") (pinfunction "2_2") (pintype "passive"))
      (node (ref "R137") (pin "2") (pinfunction "2_2") (pintype "passive"))
    )
    (net (code "75") (name "unconnected-(U100-ALERT-Pad12)") (class "Default")
      (node (ref "U100") (pin "12") (pinfunction "ALERT_12") (pintype "output"))
    )
    (net (code "76") (name "unconnected-(U108-ALERT-Pad12)") (class "Default")
      (node (ref "U108") (pin "12") (pinfunction "ALERT_12") (pintype "output"))
    )
  )
)
